# v2_0_Main.net
KiCad netlist of a schematic drawn in EAGLE
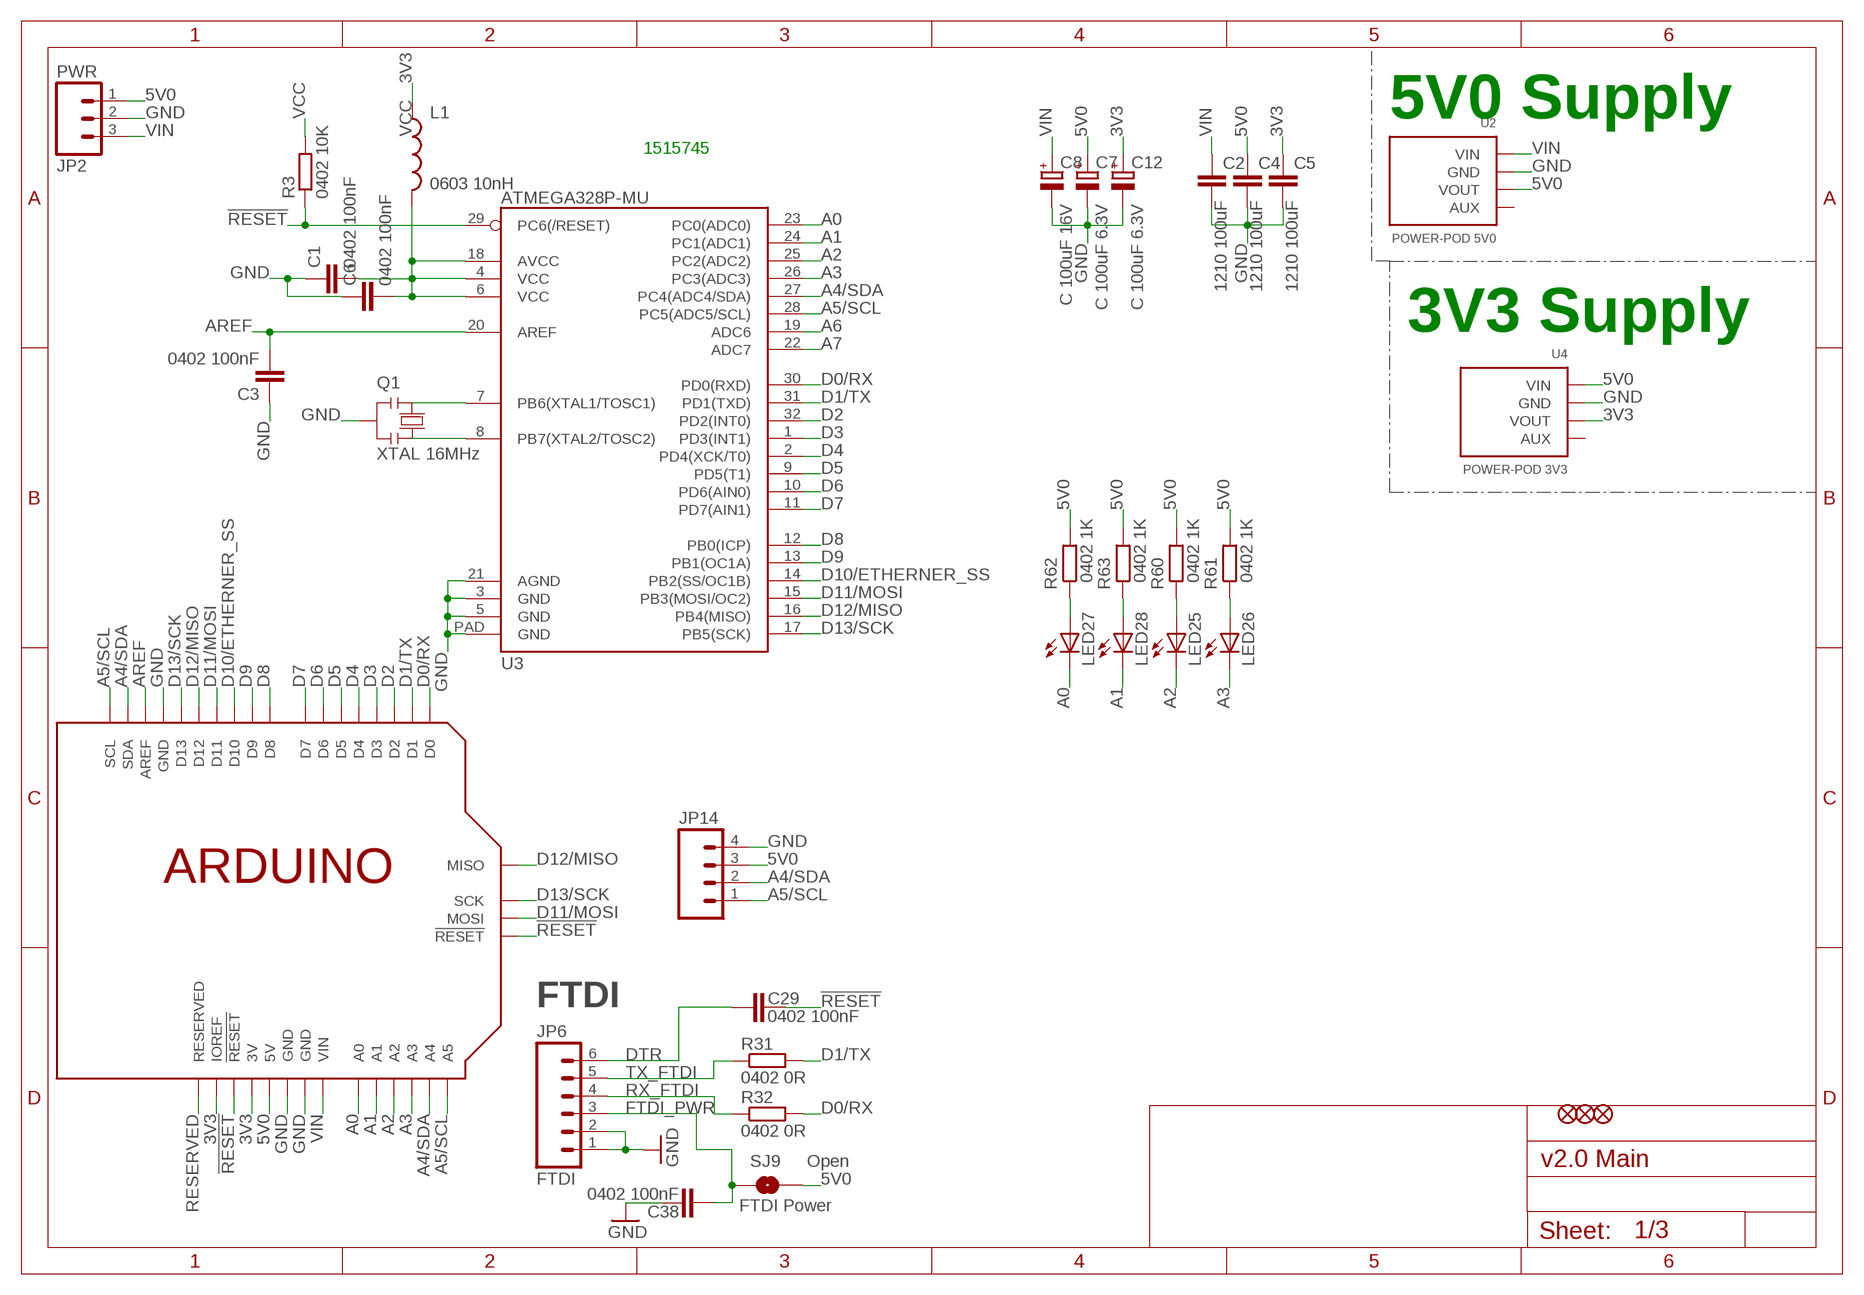
[diagram p0: schematic, sheet 1]
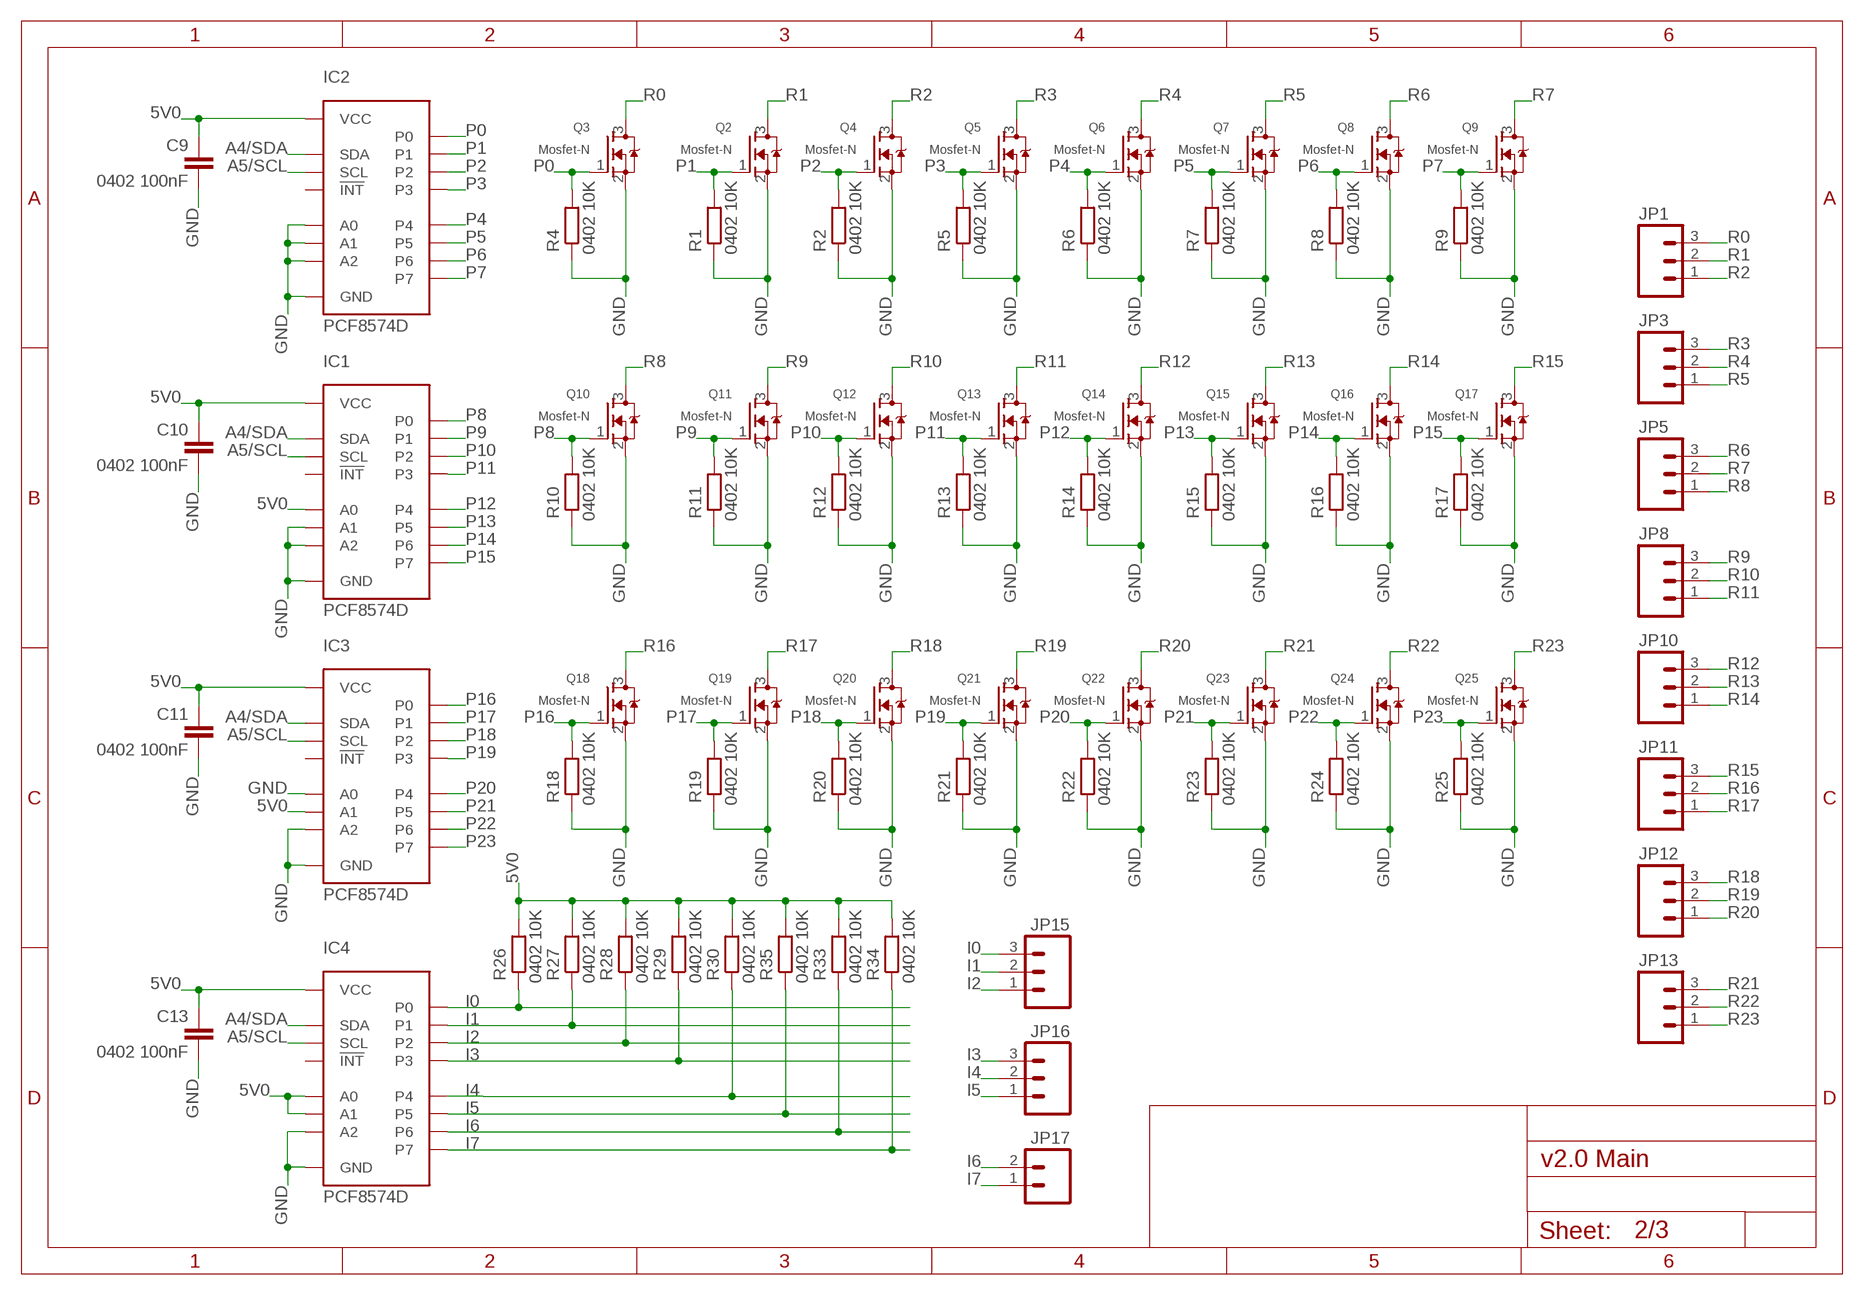
[diagram p1: schematic, sheet 2]
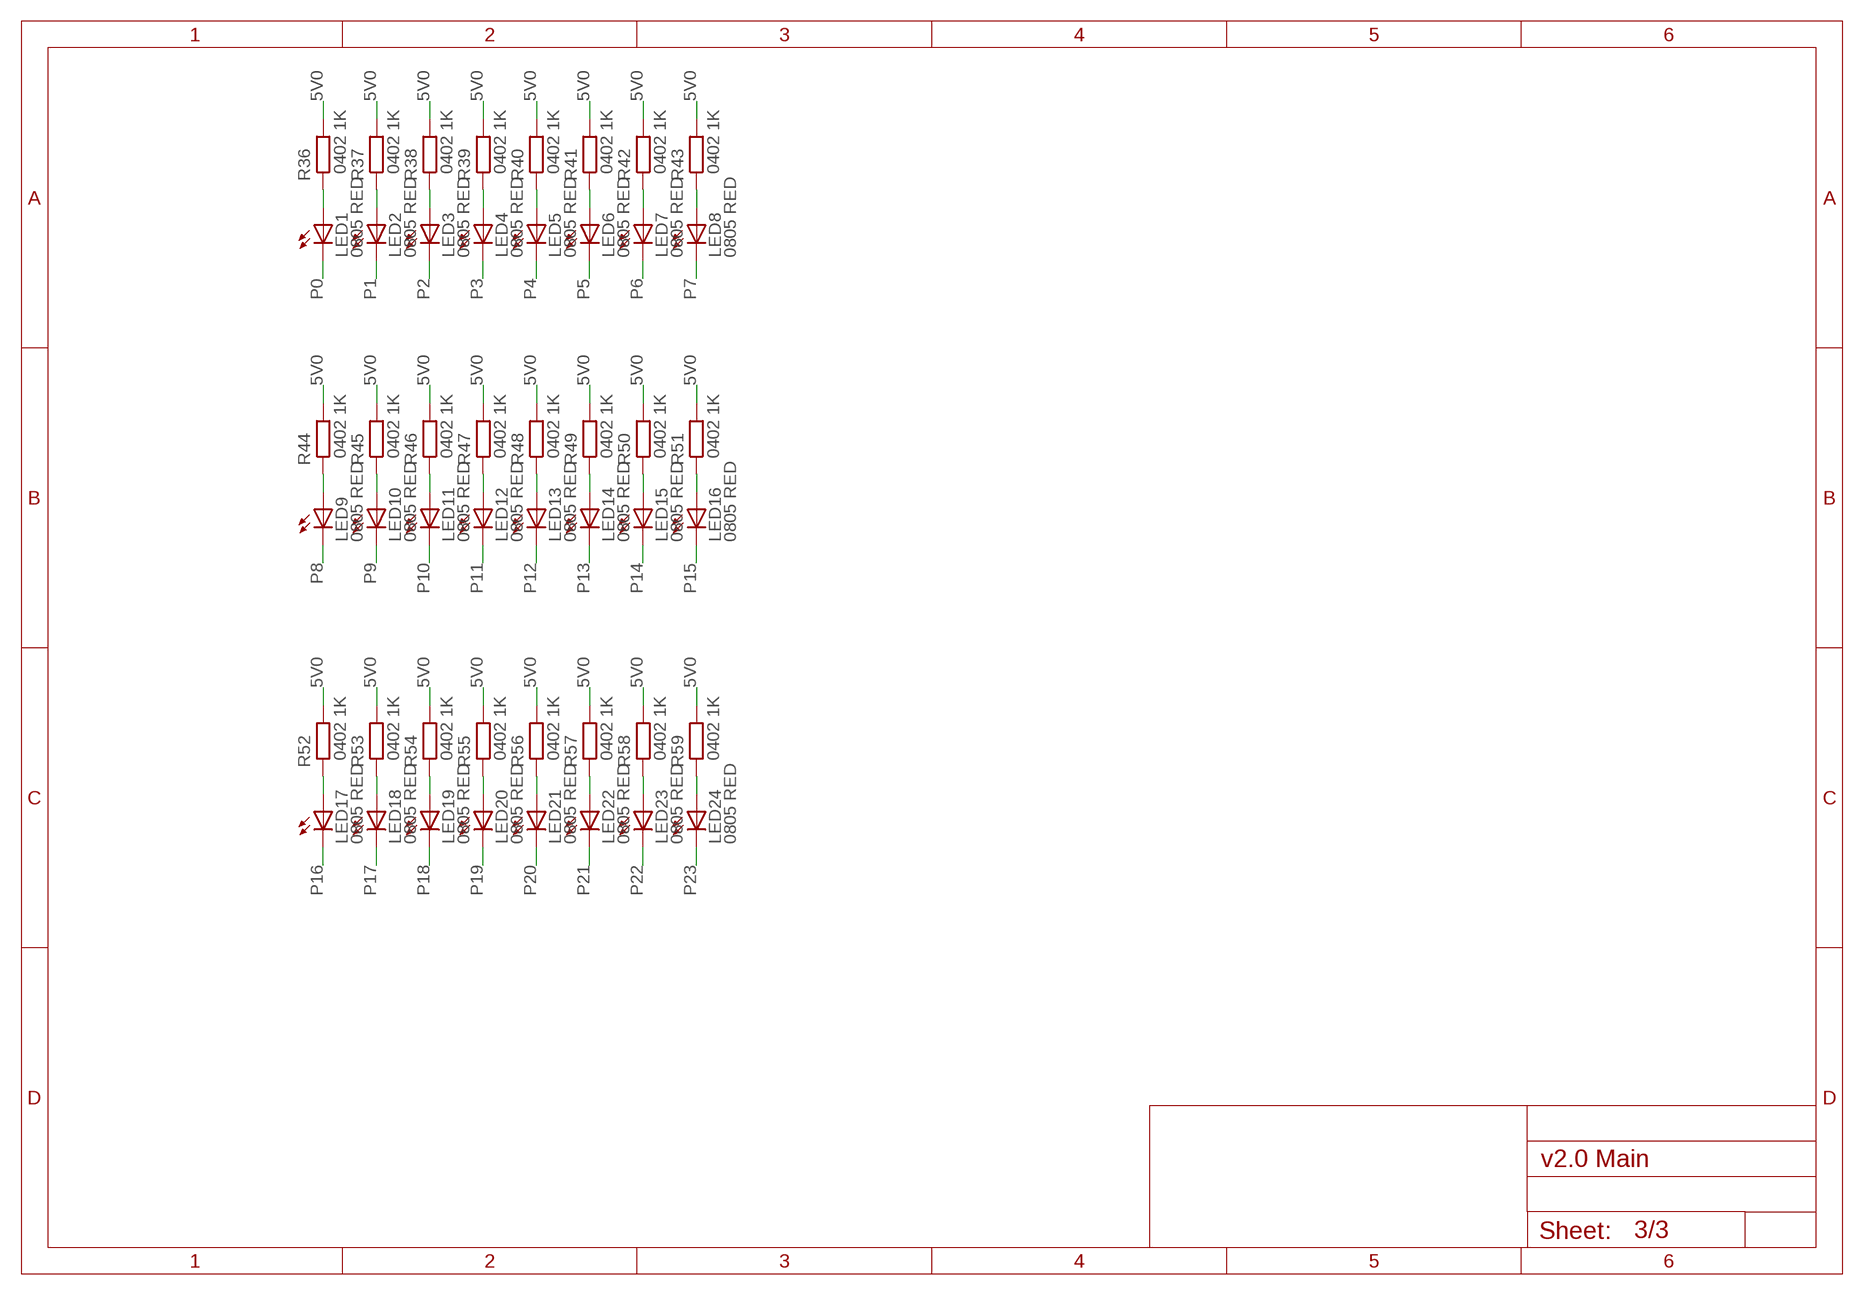
[diagram p2: schematic, sheet 3]

(export (version "E")
  (design (tool "Eeschema 10.0.6"))
  (components
    (comp (ref "LED1")
      (value "0805 RED")
      (footprint "eagle-import:LED-0805-1206")
      (libsource (lib "eagle-import") (part "LED0805-1206"))
    )
    (comp (ref "LED2")
      (value "0805 RED")
      (footprint "eagle-import:LED-0805-1206")
      (libsource (lib "eagle-import") (part "LED0805-1206"))
    )
    (comp (ref "LED3")
      (value "0805 RED")
      (footprint "eagle-import:LED-0805-1206")
      (libsource (lib "eagle-import") (part "LED0805-1206"))
    )
    (comp (ref "LED4")
      (value "0805 RED")
      (footprint "eagle-import:LED-0805-1206")
      (libsource (lib "eagle-import") (part "LED0805-1206"))
    )
    (comp (ref "LED5")
      (value "0805 RED")
      (footprint "eagle-import:LED-0805-1206")
      (libsource (lib "eagle-import") (part "LED0805-1206"))
    )
    (comp (ref "LED6")
      (value "0805 RED")
      (footprint "eagle-import:LED-0805-1206")
      (libsource (lib "eagle-import") (part "LED0805-1206"))
    )
    (comp (ref "LED7")
      (value "0805 RED")
      (footprint "eagle-import:LED-0805-1206")
      (libsource (lib "eagle-import") (part "LED0805-1206"))
    )
    (comp (ref "LED8")
      (value "0805 RED")
      (footprint "eagle-import:LED-0805-1206")
      (libsource (lib "eagle-import") (part "LED0805-1206"))
    )
    (comp (ref "LED9")
      (value "0805 RED")
      (footprint "eagle-import:LED-0805-1206")
      (libsource (lib "eagle-import") (part "LED0805-1206"))
    )
    (comp (ref "LED10")
      (value "0805 RED")
      (footprint "eagle-import:LED-0805-1206")
      (libsource (lib "eagle-import") (part "LED0805-1206"))
    )
    (comp (ref "LED11")
      (value "0805 RED")
      (footprint "eagle-import:LED-0805-1206")
      (libsource (lib "eagle-import") (part "LED0805-1206"))
    )
    (comp (ref "LED12")
      (value "0805 RED")
      (footprint "eagle-import:LED-0805-1206")
      (libsource (lib "eagle-import") (part "LED0805-1206"))
    )
    (comp (ref "LED13")
      (value "0805 RED")
      (footprint "eagle-import:LED-0805-1206")
      (libsource (lib "eagle-import") (part "LED0805-1206"))
    )
    (comp (ref "LED14")
      (value "0805 RED")
      (footprint "eagle-import:LED-0805-1206")
      (libsource (lib "eagle-import") (part "LED0805-1206"))
    )
    (comp (ref "LED15")
      (value "0805 RED")
      (footprint "eagle-import:LED-0805-1206")
      (libsource (lib "eagle-import") (part "LED0805-1206"))
    )
    (comp (ref "LED16")
      (value "0805 RED")
      (footprint "eagle-import:LED-0805-1206")
      (libsource (lib "eagle-import") (part "LED0805-1206"))
    )
    (comp (ref "LED17")
      (value "0805 RED")
      (footprint "eagle-import:LED-0805-1206")
      (libsource (lib "eagle-import") (part "LED0805-1206"))
    )
    (comp (ref "LED18")
      (value "0805 RED")
      (footprint "eagle-import:LED-0805-1206")
      (libsource (lib "eagle-import") (part "LED0805-1206"))
    )
    (comp (ref "LED19")
      (value "0805 RED")
      (footprint "eagle-import:LED-0805-1206")
      (libsource (lib "eagle-import") (part "LED0805-1206"))
    )
    (comp (ref "LED20")
      (value "0805 RED")
      (footprint "eagle-import:LED-0805-1206")
      (libsource (lib "eagle-import") (part "LED0805-1206"))
    )
    (comp (ref "LED21")
      (value "0805 RED")
      (footprint "eagle-import:LED-0805-1206")
      (libsource (lib "eagle-import") (part "LED0805-1206"))
    )
    (comp (ref "LED22")
      (value "0805 RED")
      (footprint "eagle-import:LED-0805-1206")
      (libsource (lib "eagle-import") (part "LED0805-1206"))
    )
    (comp (ref "LED23")
      (value "0805 RED")
      (footprint "eagle-import:LED-0805-1206")
      (libsource (lib "eagle-import") (part "LED0805-1206"))
    )
    (comp (ref "LED24")
      (value "0805 RED")
      (footprint "eagle-import:LED-0805-1206")
      (libsource (lib "eagle-import") (part "LED0805-1206"))
    )
    (comp (ref "R36")
      (value "0402 1K")
      (footprint "eagle-import:R0402-SMALLER")
      (libsource (lib "eagle-import") (part "R-EU_R0402-SMALLER"))
    )
    (comp (ref "R37")
      (value "0402 1K")
      (footprint "eagle-import:R0402-SMALLER")
      (libsource (lib "eagle-import") (part "R-EU_R0402-SMALLER"))
    )
    (comp (ref "R38")
      (value "0402 1K")
      (footprint "eagle-import:R0402-SMALLER")
      (libsource (lib "eagle-import") (part "R-EU_R0402-SMALLER"))
    )
    (comp (ref "R39")
      (value "0402 1K")
      (footprint "eagle-import:R0402-SMALLER")
      (libsource (lib "eagle-import") (part "R-EU_R0402-SMALLER"))
    )
    (comp (ref "R40")
      (value "0402 1K")
      (footprint "eagle-import:R0402-SMALLER")
      (libsource (lib "eagle-import") (part "R-EU_R0402-SMALLER"))
    )
    (comp (ref "R41")
      (value "0402 1K")
      (footprint "eagle-import:R0402-SMALLER")
      (libsource (lib "eagle-import") (part "R-EU_R0402-SMALLER"))
    )
    (comp (ref "R42")
      (value "0402 1K")
      (footprint "eagle-import:R0402-SMALLER")
      (libsource (lib "eagle-import") (part "R-EU_R0402-SMALLER"))
    )
    (comp (ref "R43")
      (value "0402 1K")
      (footprint "eagle-import:R0402-SMALLER")
      (libsource (lib "eagle-import") (part "R-EU_R0402-SMALLER"))
    )
    (comp (ref "R44")
      (value "0402 1K")
      (footprint "eagle-import:R0402-SMALLER")
      (libsource (lib "eagle-import") (part "R-EU_R0402-SMALLER"))
    )
    (comp (ref "R45")
      (value "0402 1K")
      (footprint "eagle-import:R0402-SMALLER")
      (libsource (lib "eagle-import") (part "R-EU_R0402-SMALLER"))
    )
    (comp (ref "R46")
      (value "0402 1K")
      (footprint "eagle-import:R0402-SMALLER")
      (libsource (lib "eagle-import") (part "R-EU_R0402-SMALLER"))
    )
    (comp (ref "R47")
      (value "0402 1K")
      (footprint "eagle-import:R0402-SMALLER")
      (libsource (lib "eagle-import") (part "R-EU_R0402-SMALLER"))
    )
    (comp (ref "R48")
      (value "0402 1K")
      (footprint "eagle-import:R0402-SMALLER")
      (libsource (lib "eagle-import") (part "R-EU_R0402-SMALLER"))
    )
    (comp (ref "R49")
      (value "0402 1K")
      (footprint "eagle-import:R0402-SMALLER")
      (libsource (lib "eagle-import") (part "R-EU_R0402-SMALLER"))
    )
    (comp (ref "R50")
      (value "0402 1K")
      (footprint "eagle-import:R0402-SMALLER")
      (libsource (lib "eagle-import") (part "R-EU_R0402-SMALLER"))
    )
    (comp (ref "R51")
      (value "0402 1K")
      (footprint "eagle-import:R0402-SMALLER")
      (libsource (lib "eagle-import") (part "R-EU_R0402-SMALLER"))
    )
    (comp (ref "R52")
      (value "0402 1K")
      (footprint "eagle-import:R0402-SMALLER")
      (libsource (lib "eagle-import") (part "R-EU_R0402-SMALLER"))
    )
    (comp (ref "R53")
      (value "0402 1K")
      (footprint "eagle-import:R0402-SMALLER")
      (libsource (lib "eagle-import") (part "R-EU_R0402-SMALLER"))
    )
    (comp (ref "R54")
      (value "0402 1K")
      (footprint "eagle-import:R0402-SMALLER")
      (libsource (lib "eagle-import") (part "R-EU_R0402-SMALLER"))
    )
    (comp (ref "R55")
      (value "0402 1K")
      (footprint "eagle-import:R0402-SMALLER")
      (libsource (lib "eagle-import") (part "R-EU_R0402-SMALLER"))
    )
    (comp (ref "R56")
      (value "0402 1K")
      (footprint "eagle-import:R0402-SMALLER")
      (libsource (lib "eagle-import") (part "R-EU_R0402-SMALLER"))
    )
    (comp (ref "R57")
      (value "0402 1K")
      (footprint "eagle-import:R0402-SMALLER")
      (libsource (lib "eagle-import") (part "R-EU_R0402-SMALLER"))
    )
    (comp (ref "R58")
      (value "0402 1K")
      (footprint "eagle-import:R0402-SMALLER")
      (libsource (lib "eagle-import") (part "R-EU_R0402-SMALLER"))
    )
    (comp (ref "R59")
      (value "0402 1K")
      (footprint "eagle-import:R0402-SMALLER")
      (libsource (lib "eagle-import") (part "R-EU_R0402-SMALLER"))
    )
    (comp (ref "C9")
      (value "0402 100nF")
      (footprint "eagle-import:C0402-SMALLER")
      (libsource (lib "eagle-import") (part "C-EUC0402-SMALLER"))
    )
    (comp (ref "C10")
      (value "0402 100nF")
      (footprint "eagle-import:C0402-SMALLER")
      (libsource (lib "eagle-import") (part "C-EUC0402-SMALLER"))
    )
    (comp (ref "C11")
      (value "0402 100nF")
      (footprint "eagle-import:C0402-SMALLER")
      (libsource (lib "eagle-import") (part "C-EUC0402-SMALLER"))
    )
    (comp (ref "C13")
      (value "0402 100nF")
      (footprint "eagle-import:C0402-SMALLER")
      (libsource (lib "eagle-import") (part "C-EUC0402-SMALLER"))
    )
    (comp (ref "IC1")
      (value "PCF8574D")
      (footprint "eagle-import:SO16-7.5MM")
      (libsource (lib "eagle-import") (part "PCF8574SO16-7/5MM"))
    )
    (comp (ref "IC2")
      (value "PCF8574D")
      (footprint "eagle-import:SO16-7.5MM")
      (libsource (lib "eagle-import") (part "PCF8574SO16-7/5MM"))
    )
    (comp (ref "IC3")
      (value "PCF8574D")
      (footprint "eagle-import:SO16-7.5MM")
      (libsource (lib "eagle-import") (part "PCF8574SO16-7/5MM"))
    )
    (comp (ref "IC4")
      (value "PCF8574D")
      (footprint "eagle-import:SO16-7.5MM")
      (libsource (lib "eagle-import") (part "PCF8574SO16-7/5MM"))
    )
    (comp (ref "JP1")
      (value "M03-SCREW-5MM")
      (footprint "eagle-import:SCREWTERMINAL-5MM-3")
      (libsource (lib "eagle-import") (part "M03-SCREW-5MM"))
    )
    (comp (ref "JP3")
      (value "M03-SCREW-5MM")
      (footprint "eagle-import:SCREWTERMINAL-5MM-3")
      (libsource (lib "eagle-import") (part "M03-SCREW-5MM"))
    )
    (comp (ref "JP5")
      (value "M03-SCREW-5MM")
      (footprint "eagle-import:SCREWTERMINAL-5MM-3")
      (libsource (lib "eagle-import") (part "M03-SCREW-5MM"))
    )
    (comp (ref "JP8")
      (value "M03-SCREW-5MM")
      (footprint "eagle-import:SCREWTERMINAL-5MM-3")
      (libsource (lib "eagle-import") (part "M03-SCREW-5MM"))
    )
    (comp (ref "JP10")
      (value "M03-SCREW-5MM")
      (footprint "eagle-import:SCREWTERMINAL-5MM-3")
      (libsource (lib "eagle-import") (part "M03-SCREW-5MM"))
    )
    (comp (ref "JP11")
      (value "M03-SCREW-5MM")
      (footprint "eagle-import:SCREWTERMINAL-5MM-3")
      (libsource (lib "eagle-import") (part "M03-SCREW-5MM"))
    )
    (comp (ref "JP12")
      (value "M03-SCREW-5MM")
      (footprint "eagle-import:SCREWTERMINAL-5MM-3")
      (libsource (lib "eagle-import") (part "M03-SCREW-5MM"))
    )
    (comp (ref "JP13")
      (value "M03-SCREW-5MM")
      (footprint "eagle-import:SCREWTERMINAL-5MM-3")
      (libsource (lib "eagle-import") (part "M03-SCREW-5MM"))
    )
    (comp (ref "JP15")
      (value "M03-SCREW-5MM")
      (footprint "eagle-import:SCREWTERMINAL-5MM-3")
      (libsource (lib "eagle-import") (part "M03-SCREW-5MM"))
    )
    (comp (ref "JP16")
      (value "M03-SCREW-5MM")
      (footprint "eagle-import:SCREWTERMINAL-5MM-3")
      (libsource (lib "eagle-import") (part "M03-SCREW-5MM"))
    )
    (comp (ref "JP17")
      (value "M025MM")
      (footprint "eagle-import:SCREWTERMINAL-5MM-2")
      (libsource (lib "eagle-import") (part "M025MM"))
    )
    (comp (ref "Q2")
      (value "Mosfet-N")
      (footprint "eagle-import:SOT23-3")
      (libsource (lib "eagle-import") (part "MOSFET-N-SOT23-SPARK"))
    )
    (comp (ref "Q3")
      (value "Mosfet-N")
      (footprint "eagle-import:SOT23-3")
      (libsource (lib "eagle-import") (part "MOSFET-N-SOT23-SPARK"))
    )
    (comp (ref "Q4")
      (value "Mosfet-N")
      (footprint "eagle-import:SOT23-3")
      (libsource (lib "eagle-import") (part "MOSFET-N-SOT23-SPARK"))
    )
    (comp (ref "Q5")
      (value "Mosfet-N")
      (footprint "eagle-import:SOT23-3")
      (libsource (lib "eagle-import") (part "MOSFET-N-SOT23-SPARK"))
    )
    (comp (ref "Q6")
      (value "Mosfet-N")
      (footprint "eagle-import:SOT23-3")
      (libsource (lib "eagle-import") (part "MOSFET-N-SOT23-SPARK"))
    )
    (comp (ref "Q7")
      (value "Mosfet-N")
      (footprint "eagle-import:SOT23-3")
      (libsource (lib "eagle-import") (part "MOSFET-N-SOT23-SPARK"))
    )
    (comp (ref "Q8")
      (value "Mosfet-N")
      (footprint "eagle-import:SOT23-3")
      (libsource (lib "eagle-import") (part "MOSFET-N-SOT23-SPARK"))
    )
    (comp (ref "Q9")
      (value "Mosfet-N")
      (footprint "eagle-import:SOT23-3")
      (libsource (lib "eagle-import") (part "MOSFET-N-SOT23-SPARK"))
    )
    (comp (ref "Q10")
      (value "Mosfet-N")
      (footprint "eagle-import:SOT23-3")
      (libsource (lib "eagle-import") (part "MOSFET-N-SOT23-SPARK"))
    )
    (comp (ref "Q11")
      (value "Mosfet-N")
      (footprint "eagle-import:SOT23-3")
      (libsource (lib "eagle-import") (part "MOSFET-N-SOT23-SPARK"))
    )
    (comp (ref "Q12")
      (value "Mosfet-N")
      (footprint "eagle-import:SOT23-3")
      (libsource (lib "eagle-import") (part "MOSFET-N-SOT23-SPARK"))
    )
    (comp (ref "Q13")
      (value "Mosfet-N")
      (footprint "eagle-import:SOT23-3")
      (libsource (lib "eagle-import") (part "MOSFET-N-SOT23-SPARK"))
    )
    (comp (ref "Q14")
      (value "Mosfet-N")
      (footprint "eagle-import:SOT23-3")
      (libsource (lib "eagle-import") (part "MOSFET-N-SOT23-SPARK"))
    )
    (comp (ref "Q15")
      (value "Mosfet-N")
      (footprint "eagle-import:SOT23-3")
      (libsource (lib "eagle-import") (part "MOSFET-N-SOT23-SPARK"))
    )
    (comp (ref "Q16")
      (value "Mosfet-N")
      (footprint "eagle-import:SOT23-3")
      (libsource (lib "eagle-import") (part "MOSFET-N-SOT23-SPARK"))
    )
    (comp (ref "Q17")
      (value "Mosfet-N")
      (footprint "eagle-import:SOT23-3")
      (libsource (lib "eagle-import") (part "MOSFET-N-SOT23-SPARK"))
    )
    (comp (ref "Q18")
      (value "Mosfet-N")
      (footprint "eagle-import:SOT23-3")
      (libsource (lib "eagle-import") (part "MOSFET-N-SOT23-SPARK"))
    )
    (comp (ref "Q19")
      (value "Mosfet-N")
      (footprint "eagle-import:SOT23-3")
      (libsource (lib "eagle-import") (part "MOSFET-N-SOT23-SPARK"))
    )
    (comp (ref "Q20")
      (value "Mosfet-N")
      (footprint "eagle-import:SOT23-3")
      (libsource (lib "eagle-import") (part "MOSFET-N-SOT23-SPARK"))
    )
    (comp (ref "Q21")
      (value "Mosfet-N")
      (footprint "eagle-import:SOT23-3")
      (libsource (lib "eagle-import") (part "MOSFET-N-SOT23-SPARK"))
    )
    (comp (ref "Q22")
      (value "Mosfet-N")
      (footprint "eagle-import:SOT23-3")
      (libsource (lib "eagle-import") (part "MOSFET-N-SOT23-SPARK"))
    )
    (comp (ref "Q23")
      (value "Mosfet-N")
      (footprint "eagle-import:SOT23-3")
      (libsource (lib "eagle-import") (part "MOSFET-N-SOT23-SPARK"))
    )
    (comp (ref "Q24")
      (value "Mosfet-N")
      (footprint "eagle-import:SOT23-3")
      (libsource (lib "eagle-import") (part "MOSFET-N-SOT23-SPARK"))
    )
    (comp (ref "Q25")
      (value "Mosfet-N")
      (footprint "eagle-import:SOT23-3")
      (libsource (lib "eagle-import") (part "MOSFET-N-SOT23-SPARK"))
    )
    (comp (ref "R1")
      (value "0402 10K")
      (footprint "eagle-import:R0402-SMALLER")
      (libsource (lib "eagle-import") (part "R-EU_R0402-SMALLER"))
    )
    (comp (ref "R2")
      (value "0402 10K")
      (footprint "eagle-import:R0402-SMALLER")
      (libsource (lib "eagle-import") (part "R-EU_R0402-SMALLER"))
    )
    (comp (ref "R4")
      (value "0402 10K")
      (footprint "eagle-import:R0402-SMALLER")
      (libsource (lib "eagle-import") (part "R-EU_R0402-SMALLER"))
    )
    (comp (ref "R5")
      (value "0402 10K")
      (footprint "eagle-import:R0402-SMALLER")
      (libsource (lib "eagle-import") (part "R-EU_R0402-SMALLER"))
    )
    (comp (ref "R6")
      (value "0402 10K")
      (footprint "eagle-import:R0402-SMALLER")
      (libsource (lib "eagle-import") (part "R-EU_R0402-SMALLER"))
    )
    (comp (ref "R7")
      (value "0402 10K")
      (footprint "eagle-import:R0402-SMALLER")
      (libsource (lib "eagle-import") (part "R-EU_R0402-SMALLER"))
    )
    (comp (ref "R8")
      (value "0402 10K")
      (footprint "eagle-import:R0402-SMALLER")
      (libsource (lib "eagle-import") (part "R-EU_R0402-SMALLER"))
    )
    (comp (ref "R9")
      (value "0402 10K")
      (footprint "eagle-import:R0402-SMALLER")
      (libsource (lib "eagle-import") (part "R-EU_R0402-SMALLER"))
    )
    (comp (ref "R10")
      (value "0402 10K")
      (footprint "eagle-import:R0402-SMALLER")
      (libsource (lib "eagle-import") (part "R-EU_R0402-SMALLER"))
    )
    (comp (ref "R11")
      (value "0402 10K")
      (footprint "eagle-import:R0402-SMALLER")
      (libsource (lib "eagle-import") (part "R-EU_R0402-SMALLER"))
    )
    (comp (ref "R12")
      (value "0402 10K")
      (footprint "eagle-import:R0402-SMALLER")
      (libsource (lib "eagle-import") (part "R-EU_R0402-SMALLER"))
    )
    (comp (ref "R13")
      (value "0402 10K")
      (footprint "eagle-import:R0402-SMALLER")
      (libsource (lib "eagle-import") (part "R-EU_R0402-SMALLER"))
    )
    (comp (ref "R14")
      (value "0402 10K")
      (footprint "eagle-import:R0402-SMALLER")
      (libsource (lib "eagle-import") (part "R-EU_R0402-SMALLER"))
    )
    (comp (ref "R15")
      (value "0402 10K")
      (footprint "eagle-import:R0402-SMALLER")
      (libsource (lib "eagle-import") (part "R-EU_R0402-SMALLER"))
    )
    (comp (ref "R16")
      (value "0402 10K")
      (footprint "eagle-import:R0402-SMALLER")
      (libsource (lib "eagle-import") (part "R-EU_R0402-SMALLER"))
    )
    (comp (ref "R17")
      (value "0402 10K")
      (footprint "eagle-import:R0402-SMALLER")
      (libsource (lib "eagle-import") (part "R-EU_R0402-SMALLER"))
    )
    (comp (ref "R18")
      (value "0402 10K")
      (footprint "eagle-import:R0402-SMALLER")
      (libsource (lib "eagle-import") (part "R-EU_R0402-SMALLER"))
    )
    (comp (ref "R19")
      (value "0402 10K")
      (footprint "eagle-import:R0402-SMALLER")
      (libsource (lib "eagle-import") (part "R-EU_R0402-SMALLER"))
    )
    (comp (ref "R20")
      (value "0402 10K")
      (footprint "eagle-import:R0402-SMALLER")
      (libsource (lib "eagle-import") (part "R-EU_R0402-SMALLER"))
    )
    (comp (ref "R21")
      (value "0402 10K")
      (footprint "eagle-import:R0402-SMALLER")
      (libsource (lib "eagle-import") (part "R-EU_R0402-SMALLER"))
    )
    (comp (ref "R22")
      (value "0402 10K")
      (footprint "eagle-import:R0402-SMALLER")
      (libsource (lib "eagle-import") (part "R-EU_R0402-SMALLER"))
    )
    (comp (ref "R23")
      (value "0402 10K")
      (footprint "eagle-import:R0402-SMALLER")
      (libsource (lib "eagle-import") (part "R-EU_R0402-SMALLER"))
    )
    (comp (ref "R24")
      (value "0402 10K")
      (footprint "eagle-import:R0402-SMALLER")
      (libsource (lib "eagle-import") (part "R-EU_R0402-SMALLER"))
    )
    (comp (ref "R25")
      (value "0402 10K")
      (footprint "eagle-import:R0402-SMALLER")
      (libsource (lib "eagle-import") (part "R-EU_R0402-SMALLER"))
    )
    (comp (ref "R26")
      (value "0402 10K")
      (footprint "eagle-import:R0402-SMALLER")
      (libsource (lib "eagle-import") (part "R-EU_R0402-SMALLER"))
    )
    (comp (ref "R27")
      (value "0402 10K")
      (footprint "eagle-import:R0402-SMALLER")
      (libsource (lib "eagle-import") (part "R-EU_R0402-SMALLER"))
    )
    (comp (ref "R28")
      (value "0402 10K")
      (footprint "eagle-import:R0402-SMALLER")
      (libsource (lib "eagle-import") (part "R-EU_R0402-SMALLER"))
    )
    (comp (ref "R29")
      (value "0402 10K")
      (footprint "eagle-import:R0402-SMALLER")
      (libsource (lib "eagle-import") (part "R-EU_R0402-SMALLER"))
    )
    (comp (ref "R30")
      (value "0402 10K")
      (footprint "eagle-import:R0402-SMALLER")
      (libsource (lib "eagle-import") (part "R-EU_R0402-SMALLER"))
    )
    (comp (ref "R33")
      (value "0402 10K")
      (footprint "eagle-import:R0402-SMALLER")
      (libsource (lib "eagle-import") (part "R-EU_R0402-SMALLER"))
    )
    (comp (ref "R34")
      (value "0402 10K")
      (footprint "eagle-import:R0402-SMALLER")
      (libsource (lib "eagle-import") (part "R-EU_R0402-SMALLER"))
    )
    (comp (ref "R35")
      (value "0402 10K")
      (footprint "eagle-import:R0402-SMALLER")
      (libsource (lib "eagle-import") (part "R-EU_R0402-SMALLER"))
    )
    (comp (ref "C1")
      (value "0402 100nF")
      (footprint "eagle-import:C0402-SMALLER")
      (libsource (lib "eagle-import") (part "C-EUC0402-SMALLER"))
    )
    (comp (ref "C2")
      (value "1210 100uF")
      (footprint "eagle-import:C1210")
      (libsource (lib "eagle-import") (part "C-EUC1210"))
    )
    (comp (ref "C3")
      (value "0402 100nF")
      (footprint "eagle-import:C0402-SMALLER")
      (libsource (lib "eagle-import") (part "C-EUC0402-SMALLER"))
    )
    (comp (ref "C4")
      (value "1210 100uF")
      (footprint "eagle-import:C1210")
      (libsource (lib "eagle-import") (part "C-EUC1210"))
    )
    (comp (ref "C5")
      (value "1210 100uF")
      (footprint "eagle-import:C1210")
      (libsource (lib "eagle-import") (part "C-EUC1210"))
    )
    (comp (ref "C6")
      (value "0402 100nF")
      (footprint "eagle-import:C0402-SMALLER")
      (libsource (lib "eagle-import") (part "C-EUC0402-SMALLER"))
    )
    (comp (ref "C7")
      (value "C 100uF 6.3V")
      (footprint "eagle-import:PANASONIC_C")
      (libsource (lib "eagle-import") (part "CPOL-EUC"))
    )
    (comp (ref "C8")
      (value "C 100uF 16V")
      (footprint "eagle-import:PANASONIC_C")
      (libsource (lib "eagle-import") (part "CPOL-EUC"))
    )
    (comp (ref "C12")
      (value "C 100uF 6.3V")
      (footprint "eagle-import:PANASONIC_C")
      (libsource (lib "eagle-import") (part "CPOL-EUC"))
    )
    (comp (ref "C29")
      (value "0402 100nF")
      (footprint "eagle-import:C0402-ARDUINO-ROUND")
      (libsource (lib "eagle-import") (part "TiLDA Mk2 Parts_C-EUC0402-ARDUINO-ROUND"))
    )
    (comp (ref "C38")
      (value "0402 100nF")
      (footprint "eagle-import:C0402-SMALLER")
      (libsource (lib "eagle-import") (part "TiLDA Mk2 Parts_C-EUC0402-SMALLER"))
    )
    (comp (ref "JP2")
      (value "PWR")
      (footprint "eagle-import:SCREWTERMINAL-5MM-3")
      (libsource (lib "eagle-import") (part "M03-SCREW-5MM"))
    )
    (comp (ref "JP4")
      (value "FIDUCIAL1X2.5-STOP")
      (footprint "eagle-import:FIDUCIAL-1X2.5-STOP")
      (libsource (lib "eagle-import") (part "FIDUCIAL1X2.5-STOP"))
    )
    (comp (ref "JP6")
      (value "FTDI")
      (footprint "eagle-import:1X06")
      (libsource (lib "eagle-import") (part "M06SIP"))
    )
    (comp (ref "JP7")
      (value "FIDUCIAL1X2.5-STOP")
      (footprint "eagle-import:FIDUCIAL-1X2.5-STOP")
      (libsource (lib "eagle-import") (part "FIDUCIAL1X2.5-STOP"))
    )
    (comp (ref "JP9")
      (value "FIDUCIAL1X2.5-STOP")
      (footprint "eagle-import:FIDUCIAL-1X2.5-STOP")
      (libsource (lib "eagle-import") (part "FIDUCIAL1X2.5-STOP"))
    )
    (comp (ref "JP14")
      (value "M04PTH")
      (footprint "eagle-import:1X04")
      (libsource (lib "eagle-import") (part "M04PTH"))
    )
    (comp (ref "L1")
      (value "0603 10nH")
      (footprint "eagle-import:C0603K-SMALL")
      (libsource (lib "eagle-import") (part "INDUCTOR0603K-SMALL"))
    )
    (comp (ref "LED25")
      (value "LED0805-1206")
      (footprint "eagle-import:LED-0805-1206")
      (libsource (lib "eagle-import") (part "LED0805-1206"))
    )
    (comp (ref "LED26")
      (value "LED0805-1206")
      (footprint "eagle-import:LED-0805-1206")
      (libsource (lib "eagle-import") (part "LED0805-1206"))
    )
    (comp (ref "LED27")
      (value "LED0805-1206")
      (footprint "eagle-import:LED-0805-1206")
      (libsource (lib "eagle-import") (part "LED0805-1206"))
    )
    (comp (ref "LED28")
      (value "LED0805-1206")
      (footprint "eagle-import:LED-0805-1206")
      (libsource (lib "eagle-import") (part "LED0805-1206"))
    )
    (comp (ref "Q1")
      (value "XTAL 16MHz")
      (footprint "eagle-import:RESONATOR")
      (libsource (lib "eagle-import") (part "RESONATORMU"))
    )
    (comp (ref "R3")
      (value "0402 10K")
      (footprint "eagle-import:R0402-SMALLER")
      (libsource (lib "eagle-import") (part "R-EU_R0402-SMALLER"))
    )
    (comp (ref "R31")
      (value "0402 0R")
      (footprint "eagle-import:R0402-ARDUINO-ROUND")
      (libsource (lib "eagle-import") (part "TiLDA Mk2 Parts_R-EU_R0402-ARDUINO-ROUND"))
    )
    (comp (ref "R32")
      (value "0402 0R")
      (footprint "eagle-import:R0402-ARDUINO-ROUND")
      (libsource (lib "eagle-import") (part "TiLDA Mk2 Parts_R-EU_R0402-ARDUINO-ROUND"))
    )
    (comp (ref "R60")
      (value "0402 1K")
      (footprint "eagle-import:R0402-SMALLER")
      (libsource (lib "eagle-import") (part "R-EU_R0402-SMALLER"))
    )
    (comp (ref "R61")
      (value "0402 1K")
      (footprint "eagle-import:R0402-SMALLER")
      (libsource (lib "eagle-import") (part "R-EU_R0402-SMALLER"))
    )
    (comp (ref "R62")
      (value "0402 1K")
      (footprint "eagle-import:R0402-SMALLER")
      (libsource (lib "eagle-import") (part "R-EU_R0402-SMALLER"))
    )
    (comp (ref "R63")
      (value "0402 1K")
      (footprint "eagle-import:R0402-SMALLER")
      (libsource (lib "eagle-import") (part "R-EU_R0402-SMALLER"))
    )
    (comp (ref "SJ9")
      (value "FTDI Power")
      (footprint "eagle-import:SJ_2S-TRACE")
      (libsource (lib "eagle-import") (part "SOLDERJUMPERTRACE"))
    )
    (comp (ref "U1")
      (value "ARDUINOSPI-REFRENCE")
      (footprint "eagle-import:ARDUINOR3-LWKTXT-REF-SPI")
      (libsource (lib "eagle-import") (part "ARDUINOSPI-REFRENCE"))
    )
    (comp (ref "U2")
      (value "POWER-POD 5V0")
      (footprint "eagle-import:POWER-POD-LANDING")
      (libsource (lib "eagle-import") (part "POWER-POD"))
    )
    (comp (ref "U3")
      (value "ATMEGA328P-MU")
      (footprint "eagle-import:MLF32-SHORT-CREAM")
      (libsource (lib "eagle-import") (part "ATMEGA328-MLF-SHORT"))
    )
    (comp (ref "U4")
      (value "POWER-POD 3V3")
      (footprint "eagle-import:POWER-POD-LANDING")
      (libsource (lib "eagle-import") (part "POWER-POD"))
    )
  )
  (nets
    (net (code "1") (name "3V3") (class "Default")
      (node (ref "C12") (pin "+") (pinfunction "+_+") (pintype "passive"))
      (node (ref "C5") (pin "1") (pinfunction "1_1") (pintype "passive"))
      (node (ref "L1") (pin "1") (pinfunction "1_1") (pintype "passive"))
      (node (ref "U1") (pin "3V") (pinfunction "3V_3V") (pintype "power_in"))
      (node (ref "U1") (pin "IOREF") (pinfunction "IOREF_IOREF") (pintype "output"))
      (node (ref "U4") (pin "3") (pinfunction "VOUT_3") (pintype "bidirectional"))
    )
    (net (code "2") (name "5V0") (class "Default")
      (node (ref "C10") (pin "1") (pinfunction "1_1") (pintype "passive"))
      (node (ref "C11") (pin "1") (pinfunction "1_1") (pintype "passive"))
      (node (ref "C13") (pin "1") (pinfunction "1_1") (pintype "passive"))
      (node (ref "C4") (pin "1") (pinfunction "1_1") (pintype "passive"))
      (node (ref "C7") (pin "+") (pinfunction "+_+") (pintype "passive"))
      (node (ref "C9") (pin "1") (pinfunction "1_1") (pintype "passive"))
      (node (ref "IC1") (pin "1") (pinfunction "A0_1") (pintype "bidirectional"))
      (node (ref "IC1") (pin "16") (pinfunction "VCC_16") (pintype "bidirectional"))
      (node (ref "IC2") (pin "16") (pinfunction "VCC_16") (pintype "bidirectional"))
      (node (ref "IC3") (pin "16") (pinfunction "VCC_16") (pintype "bidirectional"))
      (node (ref "IC3") (pin "2") (pinfunction "A1_2") (pintype "bidirectional"))
      (node (ref "IC4") (pin "1") (pinfunction "A0_1") (pintype "bidirectional"))
      (node (ref "IC4") (pin "16") (pinfunction "VCC_16") (pintype "bidirectional"))
      (node (ref "IC4") (pin "2") (pinfunction "A1_2") (pintype "bidirectional"))
      (node (ref "JP14") (pin "3") (pinfunction "3_3") (pintype "passive"))
      (node (ref "JP2") (pin "1") (pinfunction "1_1") (pintype "passive"))
      (node (ref "R26") (pin "2") (pinfunction "2_2") (pintype "passive"))
      (node (ref "R27") (pin "2") (pinfunction "2_2") (pintype "passive"))
      (node (ref "R28") (pin "2") (pinfunction "2_2") (pintype "passive"))
      (node (ref "R29") (pin "2") (pinfunction "2_2") (pintype "passive"))
      (node (ref "R30") (pin "2") (pinfunction "2_2") (pintype "passive"))
      (node (ref "R33") (pin "2") (pinfunction "2_2") (pintype "passive"))
      (node (ref "R34") (pin "2") (pinfunction "2_2") (pintype "passive"))
      (node (ref "R35") (pin "2") (pinfunction "2_2") (pintype "passive"))
      (node (ref "R36") (pin "2") (pinfunction "2_2") (pintype "passive"))
      (node (ref "R37") (pin "2") (pinfunction "2_2") (pintype "passive"))
      (node (ref "R38") (pin "2") (pinfunction "2_2") (pintype "passive"))
      (node (ref "R39") (pin "2") (pinfunction "2_2") (pintype "passive"))
      (node (ref "R40") (pin "2") (pinfunction "2_2") (pintype "passive"))
      (node (ref "R41") (pin "2") (pinfunction "2_2") (pintype "passive"))
      (node (ref "R42") (pin "2") (pinfunction "2_2") (pintype "passive"))
      (node (ref "R43") (pin "2") (pinfunction "2_2") (pintype "passive"))
      (node (ref "R44") (pin "2") (pinfunction "2_2") (pintype "passive"))
      (node (ref "R45") (pin "2") (pinfunction "2_2") (pintype "passive"))
      (node (ref "R46") (pin "2") (pinfunction "2_2") (pintype "passive"))
      (node (ref "R47") (pin "2") (pinfunction "2_2") (pintype "passive"))
      (node (ref "R48") (pin "2") (pinfunction "2_2") (pintype "passive"))
      (node (ref "R49") (pin "2") (pinfunction "2_2") (pintype "passive"))
      (node (ref "R50") (pin "2") (pinfunction "2_2") (pintype "passive"))
      (node (ref "R51") (pin "2") (pinfunction "2_2") (pintype "passive"))
      (node (ref "R52") (pin "2") (pinfunction "2_2") (pintype "passive"))
      (node (ref "R53") (pin "2") (pinfunction "2_2") (pintype "passive"))
      (node (ref "R54") (pin "2") (pinfunction "2_2") (pintype "passive"))
      (node (ref "R55") (pin "2") (pinfunction "2_2") (pintype "passive"))
      (node (ref "R56") (pin "2") (pinfunction "2_2") (pintype "passive"))
      (node (ref "R57") (pin "2") (pinfunction "2_2") (pintype "passive"))
      (node (ref "R58") (pin "2") (pinfunction "2_2") (pintype "passive"))
      (node (ref "R59") (pin "2") (pinfunction "2_2") (pintype "passive"))
      (node (ref "R60") (pin "2") (pinfunction "2_2") (pintype "passive"))
      (node (ref "R61") (pin "2") (pinfunction "2_2") (pintype "passive"))
      (node (ref "R62") (pin "2") (pinfunction "2_2") (pintype "passive"))
      (node (ref "R63") (pin "2") (pinfunction "2_2") (pintype "passive"))
      (node (ref "SJ9") (pin "2") (pinfunction "2_2") (pintype "passive"))
      (node (ref "U1") (pin "5V") (pinfunction "5V_5V") (pintype "power_in"))
      (node (ref "U1") (pin "5V@ISP") (pinfunction "5V_5V@ISP") (pintype "power_in"))
      (node (ref "U2") (pin "3") (pinfunction "VOUT_3") (pintype "bidirectional"))
      (node (ref "U4") (pin "1") (pinfunction "VIN_1") (pintype "bidirectional"))
    )
    (net (code "3") (name "A0") (class "Default")
      (node (ref "LED27") (pin "C") (pinfunction "C_C") (pintype "passive"))
      (node (ref "U1") (pin "A0") (pinfunction "A0_A0") (pintype "bidirectional"))
      (node (ref "U3") (pin "23") (pinfunction "PC0(ADC0)_23") (pintype "bidirectional"))
    )
    (net (code "4") (name "A1") (class "Default")
      (node (ref "LED28") (pin "C") (pinfunction "C_C") (pintype "passive"))
      (node (ref "U1") (pin "A1") (pinfunction "A1_A1") (pintype "bidirectional"))
      (node (ref "U3") (pin "24") (pinfunction "PC1(ADC1)_24") (pintype "bidirectional"))
    )
    (net (code "5") (name "A2") (class "Default")
      (node (ref "LED25") (pin "C") (pinfunction "C_C") (pintype "passive"))
      (node (ref "U1") (pin "A2") (pinfunction "A2_A2") (pintype "bidirectional"))
      (node (ref "U3") (pin "25") (pinfunction "PC2(ADC2)_25") (pintype "bidirectional"))
    )
    (net (code "6") (name "A3") (class "Default")
      (node (ref "LED26") (pin "C") (pinfunction "C_C") (pintype "passive"))
      (node (ref "U1") (pin "A3") (pinfunction "A3_A3") (pintype "bidirectional"))
      (node (ref "U3") (pin "26") (pinfunction "PC3(ADC3)_26") (pintype "bidirectional"))
    )
    (net (code "7") (name "A4{slash}SDA") (class "Default")
      (node (ref "IC1") (pin "15") (pinfunction "SDA_15") (pintype "bidirectional"))
      (node (ref "IC2") (pin "15") (pinfunction "SDA_15") (pintype "bidirectional"))
      (node (ref "IC3") (pin "15") (pinfunction "SDA_15") (pintype "bidirectional"))
      (node (ref "IC4") (pin "15") (pinfunction "SDA_15") (pintype "bidirectional"))
      (node (ref "JP14") (pin "2") (pinfunction "2_2") (pintype "passive"))
      (node (ref "U1") (pin "A4") (pinfunction "A4_A4") (pintype "bidirectional"))
      (node (ref "U1") (pin "SDA") (pinfunction "SDA_SDA") (pintype "bidirectional"))
      (node (ref "U3") (pin "27") (pinfunction "PC4(ADC4/SDA)_27") (pintype "bidirectional"))
    )
    (net (code "8") (name "A5{slash}SCL") (class "Default")
      (node (ref "IC1") (pin "14") (pinfunction "SCL_14") (pintype "bidirectional"))
      (node (ref "IC2") (pin "14") (pinfunction "SCL_14") (pintype "bidirectional"))
      (node (ref "IC3") (pin "14") (pinfunction "SCL_14") (pintype "bidirectional"))
      (node (ref "IC4") (pin "14") (pinfunction "SCL_14") (pintype "bidirectional"))
      (node (ref "JP14") (pin "1") (pinfunction "1_1") (pintype "passive"))
      (node (ref "U1") (pin "A5") (pinfunction "A5_A5") (pintype "bidirectional"))
      (node (ref "U1") (pin "SCL") (pinfunction "SCL_SCL") (pintype "bidirectional"))
      (node (ref "U3") (pin "28") (pinfunction "PC5(ADC5/SCL)_28") (pintype "bidirectional"))
    )
    (net (code "9") (name "A6") (class "Default")
      (node (ref "U3") (pin "19") (pinfunction "ADC6_19") (pintype "bidirectional"))
    )
    (net (code "10") (name "A7") (class "Default")
      (node (ref "U3") (pin "22") (pinfunction "ADC7_22") (pintype "bidirectional"))
    )
    (net (code "11") (name "AREF") (class "Default")
      (node (ref "C3") (pin "2") (pinfunction "2_2") (pintype "passive"))
      (node (ref "U1") (pin "AREF") (pinfunction "AREF_AREF") (pintype "bidirectional"))
      (node (ref "U3") (pin "20") (pinfunction "AREF_20") (pintype "bidirectional"))
    )
    (net (code "12") (name "D0{slash}RX") (class "Default")
      (node (ref "R32") (pin "2") (pinfunction "2_2") (pintype "passive"))
      (node (ref "U1") (pin "D0") (pinfunction "D0_D0") (pintype "bidirectional"))
      (node (ref "U3") (pin "30") (pinfunction "PD0(RXD)_30") (pintype "bidirectional"))
    )
    (net (code "13") (name "D1{slash}TX") (class "Default")
      (node (ref "R31") (pin "2") (pinfunction "2_2") (pintype "passive"))
      (node (ref "U1") (pin "D1") (pinfunction "D1_D1") (pintype "bidirectional"))
      (node (ref "U3") (pin "31") (pinfunction "PD1(TXD)_31") (pintype "bidirectional"))
    )
    (net (code "14") (name "D2") (class "Default")
      (node (ref "U1") (pin "D2") (pinfunction "D2_D2") (pintype "bidirectional"))
      (node (ref "U3") (pin "32") (pinfunction "PD2(INT0)_32") (pintype "bidirectional"))
    )
    (net (code "15") (name "D3") (class "Default")
      (node (ref "U1") (pin "D3") (pinfunction "D3_D3") (pintype "bidirectional"))
      (node (ref "U3") (pin "1") (pinfunction "PD3(INT1)_1") (pintype "bidirectional"))
    )
    (net (code "16") (name "D4") (class "Default")
      (node (ref "U1") (pin "D4") (pinfunction "D4_D4") (pintype "bidirectional"))
      (node (ref "U3") (pin "2") (pinfunction "PD4(XCK/T0)_2") (pintype "bidirectional"))
    )
    (net (code "17") (name "D5") (class "Default")
      (node (ref "U1") (pin "D5") (pinfunction "D5_D5") (pintype "bidirectional"))
      (node (ref "U3") (pin "9") (pinfunction "PD5(T1)_9") (pintype "bidirectional"))
    )
    (net (code "18") (name "D6") (class "Default")
      (node (ref "U1") (pin "D6") (pinfunction "D6_D6") (pintype "bidirectional"))
      (node (ref "U3") (pin "10") (pinfunction "PD6(AIN0)_10") (pintype "bidirectional"))
    )
    (net (code "19") (name "D7") (class "Default")
      (node (ref "U1") (pin "D7") (pinfunction "D7_D7") (pintype "bidirectional"))
      (node (ref "U3") (pin "11") (pinfunction "PD7(AIN1)_11") (pintype "bidirectional"))
    )
    (net (code "20") (name "D8") (class "Default")
      (node (ref "U1") (pin "D8") (pinfunction "D8_D8") (pintype "bidirectional"))
      (node (ref "U3") (pin "12") (pinfunction "PB0(ICP)_12") (pintype "bidirectional"))
    )
    (net (code "21") (name "D9") (class "Default")
      (node (ref "U1") (pin "D9") (pinfunction "D9_D9") (pintype "bidirectional"))
      (node (ref "U3") (pin "13") (pinfunction "PB1(OC1A)_13") (pintype "bidirectional"))
    )
    (net (code "22") (name "D10{slash}ETHERNER_SS") (class "Default")
      (node (ref "U1") (pin "D10") (pinfunction "D10_D10") (pintype "bidirectional"))
      (node (ref "U3") (pin "14") (pinfunction "PB2(SS/OC1B)_14") (pintype "bidirectional"))
    )
    (net (code "23") (name "D11{slash}MOSI") (class "Default")
      (node (ref "U1") (pin "D11") (pinfunction "D11_D11") (pintype "bidirectional"))
      (node (ref "U1") (pin "MOSI") (pinfunction "MOSI_MOSI") (pintype "bidirectional"))
      (node (ref "U3") (pin "15") (pinfunction "PB3(MOSI/OC2)_15") (pintype "bidirectional"))
    )
    (net (code "24") (name "D12{slash}MISO") (class "Default")
      (node (ref "U1") (pin "D12") (pinfunction "D12_D12") (pintype "bidirectional"))
      (node (ref "U1") (pin "MISO") (pinfunction "MISO_MISO") (pintype "bidirectional"))
      (node (ref "U3") (pin "16") (pinfunction "PB4(MISO)_16") (pintype "bidirectional"))
    )
    (net (code "25") (name "D13{slash}SCK") (class "Default")
      (node (ref "U1") (pin "D13") (pinfunction "D13_D13") (pintype "bidirectional"))
      (node (ref "U1") (pin "SCK") (pinfunction "SCK_SCK") (pintype "bidirectional"))
      (node (ref "U3") (pin "17") (pinfunction "PB5(SCK)_17") (pintype "bidirectional"))
    )
    (net (code "26") (name "DTR") (class "Default")
      (node (ref "C29") (pin "2") (pinfunction "2_2") (pintype "passive"))
      (node (ref "JP6") (pin "6") (pinfunction "6_6") (pintype "passive"))
    )
    (net (code "27") (name "FTDI_PWR") (class "Default")
      (node (ref "C38") (pin "2") (pinfunction "2_2") (pintype "passive"))
      (node (ref "JP6") (pin "3") (pinfunction "3_3") (pintype "passive"))
      (node (ref "SJ9") (pin "1") (pinfunction "1_1") (pintype "passive"))
    )
    (net (code "28") (name "GND") (class "Default")
      (node (ref "C1") (pin "1") (pinfunction "1_1") (pintype "passive"))
      (node (ref "C10") (pin "2") (pinfunction "2_2") (pintype "passive"))
      (node (ref "C11") (pin "2") (pinfunction "2_2") (pintype "passive"))
      (node (ref "C12") (pin "-") (pinfunction "-_-") (pintype "passive"))
      (node (ref "C13") (pin "2") (pinfunction "2_2") (pintype "passive"))
      (node (ref "C2") (pin "2") (pinfunction "2_2") (pintype "passive"))
      (node (ref "C3") (pin "1") (pinfunction "1_1") (pintype "passive"))
      (node (ref "C38") (pin "1") (pinfunction "1_1") (pintype "passive"))
      (node (ref "C4") (pin "2") (pinfunction "2_2") (pintype "passive"))
      (node (ref "C5") (pin "2") (pinfunction "2_2") (pintype "passive"))
      (node (ref "C6") (pin "1") (pinfunction "1_1") (pintype "passive"))
      (node (ref "C7") (pin "-") (pinfunction "-_-") (pintype "passive"))
      (node (ref "C8") (pin "-") (pinfunction "-_-") (pintype "passive"))
      (node (ref "C9") (pin "2") (pinfunction "2_2") (pintype "passive"))
      (node (ref "IC1") (pin "2") (pinfunction "A1_2") (pintype "bidirectional"))
      (node (ref "IC1") (pin "3") (pinfunction "A2_3") (pintype "bidirectional"))
      (node (ref "IC1") (pin "8") (pinfunction "GND_8") (pintype "bidirectional"))
      (node (ref "IC2") (pin "1") (pinfunction "A0_1") (pintype "bidirectional"))
      (node (ref "IC2") (pin "2") (pinfunction "A1_2") (pintype "bidirectional"))
      (node (ref "IC2") (pin "3") (pinfunction "A2_3") (pintype "bidirectional"))
      (node (ref "IC2") (pin "8") (pinfunction "GND_8") (pintype "bidirectional"))
      (node (ref "IC3") (pin "1") (pinfunction "A0_1") (pintype "bidirectional"))
      (node (ref "IC3") (pin "3") (pinfunction "A2_3") (pintype "bidirectional"))
      (node (ref "IC3") (pin "8") (pinfunction "GND_8") (pintype "bidirectional"))
      (node (ref "IC4") (pin "3") (pinfunction "A2_3") (pintype "bidirectional"))
      (node (ref "IC4") (pin "8") (pinfunction "GND_8") (pintype "bidirectional"))
      (node (ref "JP14") (pin "4") (pinfunction "4_4") (pintype "passive"))
      (node (ref "JP2") (pin "2") (pinfunction "2_2") (pintype "passive"))
      (node (ref "JP6") (pin "1") (pinfunction "1_1") (pintype "passive"))
      (node (ref "JP6") (pin "2") (pinfunction "2_2") (pintype "passive"))
      (node (ref "Q1") (pin "2") (pinfunction "2_2") (pintype "passive"))
      (node (ref "Q10") (pin "2") (pinfunction "S_2") (pintype "bidirectional"))
      (node (ref "Q11") (pin "2") (pinfunction "S_2") (pintype "bidirectional"))
      (node (ref "Q12") (pin "2") (pinfunction "S_2") (pintype "bidirectional"))
      (node (ref "Q13") (pin "2") (pinfunction "S_2") (pintype "bidirectional"))
      (node (ref "Q14") (pin "2") (pinfunction "S_2") (pintype "bidirectional"))
      (node (ref "Q15") (pin "2") (pinfunction "S_2") (pintype "bidirectional"))
      (node (ref "Q16") (pin "2") (pinfunction "S_2") (pintype "bidirectional"))
      (node (ref "Q17") (pin "2") (pinfunction "S_2") (pintype "bidirectional"))
      (node (ref "Q18") (pin "2") (pinfunction "S_2") (pintype "bidirectional"))
      (node (ref "Q19") (pin "2") (pinfunction "S_2") (pintype "bidirectional"))
      (node (ref "Q2") (pin "2") (pinfunction "S_2") (pintype "bidirectional"))
      (node (ref "Q20") (pin "2") (pinfunction "S_2") (pintype "bidirectional"))
      (node (ref "Q21") (pin "2") (pinfunction "S_2") (pintype "bidirectional"))
      (node (ref "Q22") (pin "2") (pinfunction "S_2") (pintype "bidirectional"))
      (node (ref "Q23") (pin "2") (pinfunction "S_2") (pintype "bidirectional"))
      (node (ref "Q24") (pin "2") (pinfunction "S_2") (pintype "bidirectional"))
      (node (ref "Q25") (pin "2") (pinfunction "S_2") (pintype "bidirectional"))
      (node (ref "Q3") (pin "2") (pinfunction "S_2") (pintype "bidirectional"))
      (node (ref "Q4") (pin "2") (pinfunction "S_2") (pintype "bidirectional"))
      (node (ref "Q5") (pin "2") (pinfunction "S_2") (pintype "bidirectional"))
      (node (ref "Q6") (pin "2") (pinfunction "S_2") (pintype "bidirectional"))
      (node (ref "Q7") (pin "2") (pinfunction "S_2") (pintype "bidirectional"))
      (node (ref "Q8") (pin "2") (pinfunction "S_2") (pintype "bidirectional"))
      (node (ref "Q9") (pin "2") (pinfunction "S_2") (pintype "bidirectional"))
      (node (ref "R1") (pin "1") (pinfunction "1_1") (pintype "passive"))
      (node (ref "R10") (pin "1") (pinfunction "1_1") (pintype "passive"))
      (node (ref "R11") (pin "1") (pinfunction "1_1") (pintype "passive"))
      (node (ref "R12") (pin "1") (pinfunction "1_1") (pintype "passive"))
      (node (ref "R13") (pin "1") (pinfunction "1_1") (pintype "passive"))
      (node (ref "R14") (pin "1") (pinfunction "1_1") (pintype "passive"))
      (node (ref "R15") (pin "1") (pinfunction "1_1") (pintype "passive"))
      (node (ref "R16") (pin "1") (pinfunction "1_1") (pintype "passive"))
      (node (ref "R17") (pin "1") (pinfunction "1_1") (pintype "passive"))
      (node (ref "R18") (pin "1") (pinfunction "1_1") (pintype "passive"))
      (node (ref "R19") (pin "1") (pinfunction "1_1") (pintype "passive"))
      (node (ref "R2") (pin "1") (pinfunction "1_1") (pintype "passive"))
      (node (ref "R20") (pin "1") (pinfunction "1_1") (pintype "passive"))
      (node (ref "R21") (pin "1") (pinfunction "1_1") (pintype "passive"))
      (node (ref "R22") (pin "1") (pinfunction "1_1") (pintype "passive"))
      (node (ref "R23") (pin "1") (pinfunction "1_1") (pintype "passive"))
      (node (ref "R24") (pin "1") (pinfunction "1_1") (pintype "passive"))
      (node (ref "R25") (pin "1") (pinfunction "1_1") (pintype "passive"))
      (node (ref "R4") (pin "1") (pinfunction "1_1") (pintype "passive"))
      (node (ref "R5") (pin "1") (pinfunction "1_1") (pintype "passive"))
      (node (ref "R6") (pin "1") (pinfunction "1_1") (pintype "passive"))
      (node (ref "R7") (pin "1") (pinfunction "1_1") (pintype "passive"))
      (node (ref "R8") (pin "1") (pinfunction "1_1") (pintype "passive"))
      (node (ref "R9") (pin "1") (pinfunction "1_1") (pintype "passive"))
      (node (ref "U1") (pin "GND@1") (pinfunction "GND_GND@1") (pintype "power_in"))
      (node (ref "U1") (pin "GND@2") (pinfunction "GND_GND@2") (pintype "power_in"))
      (node (ref "U1") (pin "GND@3") (pinfunction "GND_GND@3") (pintype "power_in"))
      (node (ref "U1") (pin "GND@ISP") (pinfunction "GND_GND@ISP") (pintype "power_in"))
      (node (ref "U2") (pin "2") (pinfunction "GND_2") (pintype "bidirectional"))
      (node (ref "U3") (pin "21") (pinfunction "AGND_21") (pintype "bidirectional"))
      (node (ref "U3") (pin "3") (pinfunction "GND_3") (pintype "bidirectional"))
      (node (ref "U3") (pin "5") (pinfunction "GND_5") (pintype "bidirectional"))
      (node (ref "U3") (pin "PAD") (pinfunction "GND_PAD") (pintype "bidirectional"))
      (node (ref "U4") (pin "2") (pinfunction "GND_2") (pintype "bidirectional"))
    )
    (net (code "29") (name "I0") (class "Default")
      (node (ref "IC4") (pin "4") (pinfunction "P0_4") (pintype "bidirectional"))
      (node (ref "JP15") (pin "3") (pinfunction "3_3") (pintype "passive"))
      (node (ref "R26") (pin "1") (pinfunction "1_1") (pintype "passive"))
    )
    (net (code "30") (name "I1") (class "Default")
      (node (ref "IC4") (pin "5") (pinfunction "P1_5") (pintype "bidirectional"))
      (node (ref "JP15") (pin "2") (pinfunction "2_2") (pintype "passive"))
      (node (ref "R27") (pin "1") (pinfunction "1_1") (pintype "passive"))
    )
    (net (code "31") (name "I2") (class "Default")
      (node (ref "IC4") (pin "6") (pinfunction "P2_6") (pintype "bidirectional"))
      (node (ref "JP15") (pin "1") (pinfunction "1_1") (pintype "passive"))
      (node (ref "R28") (pin "1") (pinfunction "1_1") (pintype "passive"))
    )
    (net (code "32") (name "I3") (class "Default")
      (node (ref "IC4") (pin "7") (pinfunction "P3_7") (pintype "bidirectional"))
      (node (ref "JP16") (pin "3") (pinfunction "3_3") (pintype "passive"))
      (node (ref "R29") (pin "1") (pinfunction "1_1") (pintype "passive"))
    )
    (net (code "33") (name "I4") (class "Default")
      (node (ref "IC4") (pin "9") (pinfunction "P4_9") (pintype "bidirectional"))
      (node (ref "JP16") (pin "2") (pinfunction "2_2") (pintype "passive"))
      (node (ref "R30") (pin "1") (pinfunction "1_1") (pintype "passive"))
    )
    (net (code "34") (name "I5") (class "Default")
      (node (ref "IC4") (pin "10") (pinfunction "P5_10") (pintype "bidirectional"))
      (node (ref "JP16") (pin "1") (pinfunction "1_1") (pintype "passive"))
      (node (ref "R35") (pin "1") (pinfunction "1_1") (pintype "passive"))
    )
    (net (code "35") (name "I6") (class "Default")
      (node (ref "IC4") (pin "11") (pinfunction "P6_11") (pintype "bidirectional"))
      (node (ref "JP17") (pin "2") (pinfunction "2_2") (pintype "passive"))
      (node (ref "R33") (pin "1") (pinfunction "1_1") (pintype "passive"))
    )
    (net (code "36") (name "I7") (class "Default")
      (node (ref "IC4") (pin "12") (pinfunction "P7_12") (pintype "bidirectional"))
      (node (ref "JP17") (pin "1") (pinfunction "1_1") (pintype "passive"))
      (node (ref "R34") (pin "1") (pinfunction "1_1") (pintype "passive"))
    )
    (net (code "37") (name "Net-(LED1-PadA)") (class "Default")
      (node (ref "LED1") (pin "A") (pinfunction "A_A") (pintype "passive"))
      (node (ref "R36") (pin "1") (pinfunction "1_1") (pintype "passive"))
    )
    (net (code "38") (name "Net-(LED2-PadA)") (class "Default")
      (node (ref "LED2") (pin "A") (pinfunction "A_A") (pintype "passive"))
      (node (ref "R37") (pin "1") (pinfunction "1_1") (pintype "passive"))
    )
    (net (code "39") (name "Net-(LED3-PadA)") (class "Default")
      (node (ref "LED3") (pin "A") (pinfunction "A_A") (pintype "passive"))
      (node (ref "R38") (pin "1") (pinfunction "1_1") (pintype "passive"))
    )
    (net (code "40") (name "Net-(LED4-PadA)") (class "Default")
      (node (ref "LED4") (pin "A") (pinfunction "A_A") (pintype "passive"))
      (node (ref "R39") (pin "1") (pinfunction "1_1") (pintype "passive"))
    )
    (net (code "41") (name "Net-(LED5-PadA)") (class "Default")
      (node (ref "LED5") (pin "A") (pinfunction "A_A") (pintype "passive"))
      (node (ref "R40") (pin "1") (pinfunction "1_1") (pintype "passive"))
    )
    (net (code "42") (name "Net-(LED6-PadA)") (class "Default")
      (node (ref "LED6") (pin "A") (pinfunction "A_A") (pintype "passive"))
      (node (ref "R41") (pin "1") (pinfunction "1_1") (pintype "passive"))
    )
    (net (code "43") (name "Net-(LED7-PadA)") (class "Default")
      (node (ref "LED7") (pin "A") (pinfunction "A_A") (pintype "passive"))
      (node (ref "R42") (pin "1") (pinfunction "1_1") (pintype "passive"))
    )
    (net (code "44") (name "Net-(LED8-PadA)") (class "Default")
      (node (ref "LED8") (pin "A") (pinfunction "A_A") (pintype "passive"))
      (node (ref "R43") (pin "1") (pinfunction "1_1") (pintype "passive"))
    )
    (net (code "45") (name "Net-(LED9-PadA)") (class "Default")
      (node (ref "LED9") (pin "A") (pinfunction "A_A") (pintype "passive"))
      (node (ref "R44") (pin "1") (pinfunction "1_1") (pintype "passive"))
    )
    (net (code "46") (name "Net-(LED10-PadA)") (class "Default")
      (node (ref "LED10") (pin "A") (pinfunction "A_A") (pintype "passive"))
      (node (ref "R45") (pin "1") (pinfunction "1_1") (pintype "passive"))
    )
    (net (code "47") (name "Net-(LED11-PadA)") (class "Default")
      (node (ref "LED11") (pin "A") (pinfunction "A_A") (pintype "passive"))
      (node (ref "R46") (pin "1") (pinfunction "1_1") (pintype "passive"))
    )
    (net (code "48") (name "Net-(LED12-PadA)") (class "Default")
      (node (ref "LED12") (pin "A") (pinfunction "A_A") (pintype "passive"))
      (node (ref "R47") (pin "1") (pinfunction "1_1") (pintype "passive"))
    )
    (net (code "49") (name "Net-(LED13-PadA)") (class "Default")
      (node (ref "LED13") (pin "A") (pinfunction "A_A") (pintype "passive"))
      (node (ref "R48") (pin "1") (pinfunction "1_1") (pintype "passive"))
    )
    (net (code "50") (name "Net-(LED14-PadA)") (class "Default")
      (node (ref "LED14") (pin "A") (pinfunction "A_A") (pintype "passive"))
      (node (ref "R49") (pin "1") (pinfunction "1_1") (pintype "passive"))
    )
    (net (code "51") (name "Net-(LED15-PadA)") (class "Default")
      (node (ref "LED15") (pin "A") (pinfunction "A_A") (pintype "passive"))
      (node (ref "R50") (pin "1") (pinfunction "1_1") (pintype "passive"))
    )
    (net (code "52") (name "Net-(LED16-PadA)") (class "Default")
      (node (ref "LED16") (pin "A") (pinfunction "A_A") (pintype "passive"))
      (node (ref "R51") (pin "1") (pinfunction "1_1") (pintype "passive"))
    )
    (net (code "53") (name "Net-(LED17-PadA)") (class "Default")
      (node (ref "LED17") (pin "A") (pinfunction "A_A") (pintype "passive"))
      (node (ref "R52") (pin "1") (pinfunction "1_1") (pintype "passive"))
    )
    (net (code "54") (name "Net-(LED18-PadA)") (class "Default")
      (node (ref "LED18") (pin "A") (pinfunction "A_A") (pintype "passive"))
      (node (ref "R53") (pin "1") (pinfunction "1_1") (pintype "passive"))
    )
    (net (code "55") (name "Net-(LED19-PadA)") (class "Default")
      (node (ref "LED19") (pin "A") (pinfunction "A_A") (pintype "passive"))
      (node (ref "R54") (pin "1") (pinfunction "1_1") (pintype "passive"))
    )
    (net (code "56") (name "Net-(LED20-PadA)") (class "Default")
      (node (ref "LED20") (pin "A") (pinfunction "A_A") (pintype "passive"))
      (node (ref "R55") (pin "1") (pinfunction "1_1") (pintype "passive"))
    )
    (net (code "57") (name "Net-(LED21-PadA)") (class "Default")
      (node (ref "LED21") (pin "A") (pinfunction "A_A") (pintype "passive"))
      (node (ref "R56") (pin "1") (pinfunction "1_1") (pintype "passive"))
    )
    (net (code "58") (name "Net-(LED22-PadA)") (class "Default")
      (node (ref "LED22") (pin "A") (pinfunction "A_A") (pintype "passive"))
      (node (ref "R57") (pin "1") (pinfunction "1_1") (pintype "passive"))
    )
    (net (code "59") (name "Net-(LED23-PadA)") (class "Default")
      (node (ref "LED23") (pin "A") (pinfunction "A_A") (pintype "passive"))
      (node (ref "R58") (pin "1") (pinfunction "1_1") (pintype "passive"))
    )
    (net (code "60") (name "Net-(LED24-PadA)") (class "Default")
      (node (ref "LED24") (pin "A") (pinfunction "A_A") (pintype "passive"))
      (node (ref "R59") (pin "1") (pinfunction "1_1") (pintype "passive"))
    )
    (net (code "61") (name "Net-(LED25-PadA)") (class "Default")
      (node (ref "LED25") (pin "A") (pinfunction "A_A") (pintype "passive"))
      (node (ref "R60") (pin "1") (pinfunction "1_1") (pintype "passive"))
    )
    (net (code "62") (name "Net-(LED26-PadA)") (class "Default")
      (node (ref "LED26") (pin "A") (pinfunction "A_A") (pintype "passive"))
      (node (ref "R61") (pin "1") (pinfunction "1_1") (pintype "passive"))
    )
    (net (code "63") (name "Net-(LED27-PadA)") (class "Default")
      (node (ref "LED27") (pin "A") (pinfunction "A_A") (pintype "passive"))
      (node (ref "R62") (pin "1") (pinfunction "1_1") (pintype "passive"))
    )
    (net (code "64") (name "Net-(LED28-PadA)") (class "Default")
      (node (ref "LED28") (pin "A") (pinfunction "A_A") (pintype "passive"))
      (node (ref "R63") (pin "1") (pinfunction "1_1") (pintype "passive"))
    )
    (net (code "65") (name "Net-(U3-PB6(XTAL1{slash}TOSC1))") (class "Default")
      (node (ref "Q1") (pin "1") (pinfunction "1_1") (pintype "passive"))
      (node (ref "U3") (pin "7") (pinfunction "PB6(XTAL1/TOSC1)_7") (pintype "bidirectional"))
    )
    (net (code "66") (name "Net-(U3-PB7(XTAL2{slash}TOSC2))") (class "Default")
      (node (ref "Q1") (pin "3") (pinfunction "3_3") (pintype "passive"))
      (node (ref "U3") (pin "8") (pinfunction "PB7(XTAL2/TOSC2)_8") (pintype "bidirectional"))
    )
    (net (code "67") (name "P0") (class "Default")
      (node (ref "IC2") (pin "4") (pinfunction "P0_4") (pintype "bidirectional"))
      (node (ref "LED1") (pin "C") (pinfunction "C_C") (pintype "passive"))
      (node (ref "Q3") (pin "1") (pinfunction "G_1") (pintype "bidirectional"))
      (node (ref "R4") (pin "2") (pinfunction "2_2") (pintype "passive"))
    )
    (net (code "68") (name "P1") (class "Default")
      (node (ref "IC2") (pin "5") (pinfunction "P1_5") (pintype "bidirectional"))
      (node (ref "LED2") (pin "C") (pinfunction "C_C") (pintype "passive"))
      (node (ref "Q2") (pin "1") (pinfunction "G_1") (pintype "bidirectional"))
      (node (ref "R1") (pin "2") (pinfunction "2_2") (pintype "passive"))
    )
    (net (code "69") (name "P2") (class "Default")
      (node (ref "IC2") (pin "6") (pinfunction "P2_6") (pintype "bidirectional"))
      (node (ref "LED3") (pin "C") (pinfunction "C_C") (pintype "passive"))
      (node (ref "Q4") (pin "1") (pinfunction "G_1") (pintype "bidirectional"))
      (node (ref "R2") (pin "2") (pinfunction "2_2") (pintype "passive"))
    )
    (net (code "70") (name "P3") (class "Default")
      (node (ref "IC2") (pin "7") (pinfunction "P3_7") (pintype "bidirectional"))
      (node (ref "LED4") (pin "C") (pinfunction "C_C") (pintype "passive"))
      (node (ref "Q5") (pin "1") (pinfunction "G_1") (pintype "bidirectional"))
      (node (ref "R5") (pin "2") (pinfunction "2_2") (pintype "passive"))
    )
    (net (code "71") (name "P4") (class "Default")
      (node (ref "IC2") (pin "9") (pinfunction "P4_9") (pintype "bidirectional"))
      (node (ref "LED5") (pin "C") (pinfunction "C_C") (pintype "passive"))
      (node (ref "Q6") (pin "1") (pinfunction "G_1") (pintype "bidirectional"))
      (node (ref "R6") (pin "2") (pinfunction "2_2") (pintype "passive"))
    )
    (net (code "72") (name "P5") (class "Default")
      (node (ref "IC2") (pin "10") (pinfunction "P5_10") (pintype "bidirectional"))
      (node (ref "LED6") (pin "C") (pinfunction "C_C") (pintype "passive"))
      (node (ref "Q7") (pin "1") (pinfunction "G_1") (pintype "bidirectional"))
      (node (ref "R7") (pin "2") (pinfunction "2_2") (pintype "passive"))
    )
    (net (code "73") (name "P6") (class "Default")
      (node (ref "IC2") (pin "11") (pinfunction "P6_11") (pintype "bidirectional"))
      (node (ref "LED7") (pin "C") (pinfunction "C_C") (pintype "passive"))
      (node (ref "Q8") (pin "1") (pinfunction "G_1") (pintype "bidirectional"))
      (node (ref "R8") (pin "2") (pinfunction "2_2") (pintype "passive"))
    )
    (net (code "74") (name "P7") (class "Default")
      (node (ref "IC2") (pin "12") (pinfunction "P7_12") (pintype "bidirectional"))
      (node (ref "LED8") (pin "C") (pinfunction "C_C") (pintype "passive"))
      (node (ref "Q9") (pin "1") (pinfunction "G_1") (pintype "bidirectional"))
      (node (ref "R9") (pin "2") (pinfunction "2_2") (pintype "passive"))
    )
    (net (code "75") (name "P8") (class "Default")
      (node (ref "IC1") (pin "4") (pinfunction "P0_4") (pintype "bidirectional"))
      (node (ref "LED9") (pin "C") (pinfunction "C_C") (pintype "passive"))
      (node (ref "Q10") (pin "1") (pinfunction "G_1") (pintype "bidirectional"))
      (node (ref "R10") (pin "2") (pinfunction "2_2") (pintype "passive"))
    )
    (net (code "76") (name "P9") (class "Default")
      (node (ref "IC1") (pin "5") (pinfunction "P1_5") (pintype "bidirectional"))
      (node (ref "LED10") (pin "C") (pinfunction "C_C") (pintype "passive"))
      (node (ref "Q11") (pin "1") (pinfunction "G_1") (pintype "bidirectional"))
      (node (ref "R11") (pin "2") (pinfunction "2_2") (pintype "passive"))
    )
    (net (code "77") (name "P10") (class "Default")
      (node (ref "IC1") (pin "6") (pinfunction "P2_6") (pintype "bidirectional"))
      (node (ref "LED11") (pin "C") (pinfunction "C_C") (pintype "passive"))
      (node (ref "Q12") (pin "1") (pinfunction "G_1") (pintype "bidirectional"))
      (node (ref "R12") (pin "2") (pinfunction "2_2") (pintype "passive"))
    )
    (net (code "78") (name "P11") (class "Default")
      (node (ref "IC1") (pin "7") (pinfunction "P3_7") (pintype "bidirectional"))
      (node (ref "LED12") (pin "C") (pinfunction "C_C") (pintype "passive"))
      (node (ref "Q13") (pin "1") (pinfunction "G_1") (pintype "bidirectional"))
      (node (ref "R13") (pin "2") (pinfunction "2_2") (pintype "passive"))
    )
    (net (code "79") (name "P12") (class "Default")
      (node (ref "IC1") (pin "9") (pinfunction "P4_9") (pintype "bidirectional"))
      (node (ref "LED13") (pin "C") (pinfunction "C_C") (pintype "passive"))
      (node (ref "Q14") (pin "1") (pinfunction "G_1") (pintype "bidirectional"))
      (node (ref "R14") (pin "2") (pinfunction "2_2") (pintype "passive"))
    )
    (net (code "80") (name "P13") (class "Default")
      (node (ref "IC1") (pin "10") (pinfunction "P5_10") (pintype "bidirectional"))
      (node (ref "LED14") (pin "C") (pinfunction "C_C") (pintype "passive"))
      (node (ref "Q15") (pin "1") (pinfunction "G_1") (pintype "bidirectional"))
      (node (ref "R15") (pin "2") (pinfunction "2_2") (pintype "passive"))
    )
    (net (code "81") (name "P14") (class "Default")
      (node (ref "IC1") (pin "11") (pinfunction "P6_11") (pintype "bidirectional"))
      (node (ref "LED15") (pin "C") (pinfunction "C_C") (pintype "passive"))
      (node (ref "Q16") (pin "1") (pinfunction "G_1") (pintype "bidirectional"))
      (node (ref "R16") (pin "2") (pinfunction "2_2") (pintype "passive"))
    )
    (net (code "82") (name "P15") (class "Default")
      (node (ref "IC1") (pin "12") (pinfunction "P7_12") (pintype "bidirectional"))
      (node (ref "LED16") (pin "C") (pinfunction "C_C") (pintype "passive"))
      (node (ref "Q17") (pin "1") (pinfunction "G_1") (pintype "bidirectional"))
      (node (ref "R17") (pin "2") (pinfunction "2_2") (pintype "passive"))
    )
    (net (code "83") (name "P16") (class "Default")
      (node (ref "IC3") (pin "4") (pinfunction "P0_4") (pintype "bidirectional"))
      (node (ref "LED17") (pin "C") (pinfunction "C_C") (pintype "passive"))
      (node (ref "Q18") (pin "1") (pinfunction "G_1") (pintype "bidirectional"))
      (node (ref "R18") (pin "2") (pinfunction "2_2") (pintype "passive"))
    )
    (net (code "84") (name "P17") (class "Default")
      (node (ref "IC3") (pin "5") (pinfunction "P1_5") (pintype "bidirectional"))
      (node (ref "LED18") (pin "C") (pinfunction "C_C") (pintype "passive"))
      (node (ref "Q19") (pin "1") (pinfunction "G_1") (pintype "bidirectional"))
      (node (ref "R19") (pin "2") (pinfunction "2_2") (pintype "passive"))
    )
    (net (code "85") (name "P18") (class "Default")
      (node (ref "IC3") (pin "6") (pinfunction "P2_6") (pintype "bidirectional"))
      (node (ref "LED19") (pin "C") (pinfunction "C_C") (pintype "passive"))
      (node (ref "Q20") (pin "1") (pinfunction "G_1") (pintype "bidirectional"))
      (node (ref "R20") (pin "2") (pinfunction "2_2") (pintype "passive"))
    )
    (net (code "86") (name "P19") (class "Default")
      (node (ref "IC3") (pin "7") (pinfunction "P3_7") (pintype "bidirectional"))
      (node (ref "LED20") (pin "C") (pinfunction "C_C") (pintype "passive"))
      (node (ref "Q21") (pin "1") (pinfunction "G_1") (pintype "bidirectional"))
      (node (ref "R21") (pin "2") (pinfunction "2_2") (pintype "passive"))
    )
    (net (code "87") (name "P20") (class "Default")
      (node (ref "IC3") (pin "9") (pinfunction "P4_9") (pintype "bidirectional"))
      (node (ref "LED21") (pin "C") (pinfunction "C_C") (pintype "passive"))
      (node (ref "Q22") (pin "1") (pinfunction "G_1") (pintype "bidirectional"))
      (node (ref "R22") (pin "2") (pinfunction "2_2") (pintype "passive"))
    )
    (net (code "88") (name "P21") (class "Default")
      (node (ref "IC3") (pin "10") (pinfunction "P5_10") (pintype "bidirectional"))
      (node (ref "LED22") (pin "C") (pinfunction "C_C") (pintype "passive"))
      (node (ref "Q23") (pin "1") (pinfunction "G_1") (pintype "bidirectional"))
      (node (ref "R23") (pin "2") (pinfunction "2_2") (pintype "passive"))
    )
    (net (code "89") (name "P22") (class "Default")
      (node (ref "IC3") (pin "11") (pinfunction "P6_11") (pintype "bidirectional"))
      (node (ref "LED23") (pin "C") (pinfunction "C_C") (pintype "passive"))
      (node (ref "Q24") (pin "1") (pinfunction "G_1") (pintype "bidirectional"))
      (node (ref "R24") (pin "2") (pinfunction "2_2") (pintype "passive"))
    )
    (net (code "90") (name "P23") (class "Default")
      (node (ref "IC3") (pin "12") (pinfunction "P7_12") (pintype "bidirectional"))
      (node (ref "LED24") (pin "C") (pinfunction "C_C") (pintype "passive"))
      (node (ref "Q25") (pin "1") (pinfunction "G_1") (pintype "bidirectional"))
      (node (ref "R25") (pin "2") (pinfunction "2_2") (pintype "passive"))
    )
    (net (code "91") (name "R0") (class "Default")
      (node (ref "JP1") (pin "3") (pinfunction "3_3") (pintype "passive"))
      (node (ref "Q3") (pin "3") (pinfunction "D_3") (pintype "bidirectional"))
    )
    (net (code "92") (name "R1") (class "Default")
      (node (ref "JP1") (pin "2") (pinfunction "2_2") (pintype "passive"))
      (node (ref "Q2") (pin "3") (pinfunction "D_3") (pintype "bidirectional"))
    )
    (net (code "93") (name "R2") (class "Default")
      (node (ref "JP1") (pin "1") (pinfunction "1_1") (pintype "passive"))
      (node (ref "Q4") (pin "3") (pinfunction "D_3") (pintype "bidirectional"))
    )
    (net (code "94") (name "R3") (class "Default")
      (node (ref "JP3") (pin "3") (pinfunction "3_3") (pintype "passive"))
      (node (ref "Q5") (pin "3") (pinfunction "D_3") (pintype "bidirectional"))
    )
    (net (code "95") (name "R4") (class "Default")
      (node (ref "JP3") (pin "2") (pinfunction "2_2") (pintype "passive"))
      (node (ref "Q6") (pin "3") (pinfunction "D_3") (pintype "bidirectional"))
    )
    (net (code "96") (name "R5") (class "Default")
      (node (ref "JP3") (pin "1") (pinfunction "1_1") (pintype "passive"))
      (node (ref "Q7") (pin "3") (pinfunction "D_3") (pintype "bidirectional"))
    )
    (net (code "97") (name "R6") (class "Default")
      (node (ref "JP5") (pin "3") (pinfunction "3_3") (pintype "passive"))
      (node (ref "Q8") (pin "3") (pinfunction "D_3") (pintype "bidirectional"))
    )
    (net (code "98") (name "R7") (class "Default")
      (node (ref "JP5") (pin "2") (pinfunction "2_2") (pintype "passive"))
      (node (ref "Q9") (pin "3") (pinfunction "D_3") (pintype "bidirectional"))
    )
    (net (code "99") (name "R8") (class "Default")
      (node (ref "JP5") (pin "1") (pinfunction "1_1") (pintype "passive"))
      (node (ref "Q10") (pin "3") (pinfunction "D_3") (pintype "bidirectional"))
    )
    (net (code "100") (name "R9") (class "Default")
      (node (ref "JP8") (pin "3") (pinfunction "3_3") (pintype "passive"))
      (node (ref "Q11") (pin "3") (pinfunction "D_3") (pintype "bidirectional"))
    )
    (net (code "101") (name "R10") (class "Default")
      (node (ref "JP8") (pin "2") (pinfunction "2_2") (pintype "passive"))
      (node (ref "Q12") (pin "3") (pinfunction "D_3") (pintype "bidirectional"))
    )
    (net (code "102") (name "R11") (class "Default")
      (node (ref "JP8") (pin "1") (pinfunction "1_1") (pintype "passive"))
      (node (ref "Q13") (pin "3") (pinfunction "D_3") (pintype "bidirectional"))
    )
    (net (code "103") (name "R12") (class "Default")
      (node (ref "JP10") (pin "3") (pinfunction "3_3") (pintype "passive"))
      (node (ref "Q14") (pin "3") (pinfunction "D_3") (pintype "bidirectional"))
    )
    (net (code "104") (name "R13") (class "Default")
      (node (ref "JP10") (pin "2") (pinfunction "2_2") (pintype "passive"))
      (node (ref "Q15") (pin "3") (pinfunction "D_3") (pintype "bidirectional"))
    )
    (net (code "105") (name "R14") (class "Default")
      (node (ref "JP10") (pin "1") (pinfunction "1_1") (pintype "passive"))
      (node (ref "Q16") (pin "3") (pinfunction "D_3") (pintype "bidirectional"))
    )
    (net (code "106") (name "R15") (class "Default")
      (node (ref "JP11") (pin "3") (pinfunction "3_3") (pintype "passive"))
      (node (ref "Q17") (pin "3") (pinfunction "D_3") (pintype "bidirectional"))
    )
    (net (code "107") (name "R16") (class "Default")
      (node (ref "JP11") (pin "2") (pinfunction "2_2") (pintype "passive"))
      (node (ref "Q18") (pin "3") (pinfunction "D_3") (pintype "bidirectional"))
    )
    (net (code "108") (name "R17") (class "Default")
      (node (ref "JP11") (pin "1") (pinfunction "1_1") (pintype "passive"))
      (node (ref "Q19") (pin "3") (pinfunction "D_3") (pintype "bidirectional"))
    )
    (net (code "109") (name "R18") (class "Default")
      (node (ref "JP12") (pin "3") (pinfunction "3_3") (pintype "passive"))
      (node (ref "Q20") (pin "3") (pinfunction "D_3") (pintype "bidirectional"))
    )
    (net (code "110") (name "R19") (class "Default")
      (node (ref "JP12") (pin "2") (pinfunction "2_2") (pintype "passive"))
      (node (ref "Q21") (pin "3") (pinfunction "D_3") (pintype "bidirectional"))
    )
    (net (code "111") (name "R20") (class "Default")
      (node (ref "JP12") (pin "1") (pinfunction "1_1") (pintype "passive"))
      (node (ref "Q22") (pin "3") (pinfunction "D_3") (pintype "bidirectional"))
    )
    (net (code "112") (name "R21") (class "Default")
      (node (ref "JP13") (pin "3") (pinfunction "3_3") (pintype "passive"))
      (node (ref "Q23") (pin "3") (pinfunction "D_3") (pintype "bidirectional"))
    )
    (net (code "113") (name "R22") (class "Default")
      (node (ref "JP13") (pin "2") (pinfunction "2_2") (pintype "passive"))
      (node (ref "Q24") (pin "3") (pinfunction "D_3") (pintype "bidirectional"))
    )
    (net (code "114") (name "R23") (class "Default")
      (node (ref "JP13") (pin "1") (pinfunction "1_1") (pintype "passive"))
      (node (ref "Q25") (pin "3") (pinfunction "D_3") (pintype "bidirectional"))
    )
    (net (code "116") (name "RESERVED") (class "Default")
      (node (ref "U1") (pin "RESERVED") (pinfunction "RESERVED_RESERVED") (pintype "no_connect"))
    )
    (net (code "117") (name "RX_FTDI") (class "Default")
      (node (ref "JP6") (pin "4") (pinfunction "4_4") (pintype "passive"))
      (node (ref "R32") (pin "1") (pinfunction "1_1") (pintype "passive"))
    )
    (net (code "118") (name "TX_FTDI") (class "Default")
      (node (ref "JP6") (pin "5") (pinfunction "5_5") (pintype "passive"))
      (node (ref "R31") (pin "1") (pinfunction "1_1") (pintype "passive"))
    )
    (net (code "119") (name "VCC") (class "Default")
      (node (ref "C1") (pin "2") (pinfunction "2_2") (pintype "passive"))
      (node (ref "C6") (pin "2") (pinfunction "2_2") (pintype "passive"))
      (node (ref "L1") (pin "2") (pinfunction "2_2") (pintype "passive"))
      (node (ref "R3") (pin "2") (pinfunction "2_2") (pintype "passive"))
      (node (ref "U3") (pin "18") (pinfunction "AVCC_18") (pintype "bidirectional"))
      (node (ref "U3") (pin "4") (pinfunction "VCC_4") (pintype "bidirectional"))
      (node (ref "U3") (pin "6") (pinfunction "VCC_6") (pintype "bidirectional"))
    )
    (net (code "120") (name "VIN") (class "Default")
      (node (ref "C2") (pin "1") (pinfunction "1_1") (pintype "passive"))
      (node (ref "C8") (pin "+") (pinfunction "+_+") (pintype "passive"))
      (node (ref "JP2") (pin "3") (pinfunction "3_3") (pintype "passive"))
      (node (ref "U1") (pin "VIN") (pinfunction "VIN_VIN") (pintype "power_in"))
      (node (ref "U2") (pin "1") (pinfunction "VIN_1") (pintype "bidirectional"))
    )
    (net (code "121") (name "unconnected-(IC1-~{INT}-Pad13)") (class "Default")
      (node (ref "IC1") (pin "13") (pinfunction "~{INT}_13") (pintype "bidirectional"))
    )
    (net (code "122") (name "unconnected-(IC2-~{INT}-Pad13)") (class "Default")
      (node (ref "IC2") (pin "13") (pinfunction "~{INT}_13") (pintype "bidirectional"))
    )
    (net (code "123") (name "unconnected-(IC3-~{INT}-Pad13)") (class "Default")
      (node (ref "IC3") (pin "13") (pinfunction "~{INT}_13") (pintype "bidirectional"))
    )
    (net (code "124") (name "unconnected-(IC4-~{INT}-Pad13)") (class "Default")
      (node (ref "IC4") (pin "13") (pinfunction "~{INT}_13") (pintype "bidirectional"))
    )
    (net (code "125") (name "unconnected-(U2-AUX-Pad4)") (class "Default")
      (node (ref "U2") (pin "4") (pinfunction "AUX_4") (pintype "bidirectional"))
    )
    (net (code "126") (name "unconnected-(U4-AUX-Pad4)") (class "Default")
      (node (ref "U4") (pin "4") (pinfunction "AUX_4") (pintype "bidirectional"))
    )
    (net (code "127") (name "~{RESET}") (class "Default")
      (node (ref "C29") (pin "1") (pinfunction "1_1") (pintype "passive"))
      (node (ref "R3") (pin "1") (pinfunction "1_1") (pintype "passive"))
      (node (ref "U1") (pin "!RESET") (pinfunction "~{RESET}_!RESET") (pintype "bidirectional"))
      (node (ref "U1") (pin "!RESET@ISP") (pinfunction "~{RESET}_!RESET@ISP") (pintype "bidirectional"))
      (node (ref "U3") (pin "29") (pinfunction "PC6(/RESET)_29") (pintype "bidirectional"))
    )
  )
)
